# STM32H743IIT6.net
KiCad netlist of a schematic drawn in Altium Designer
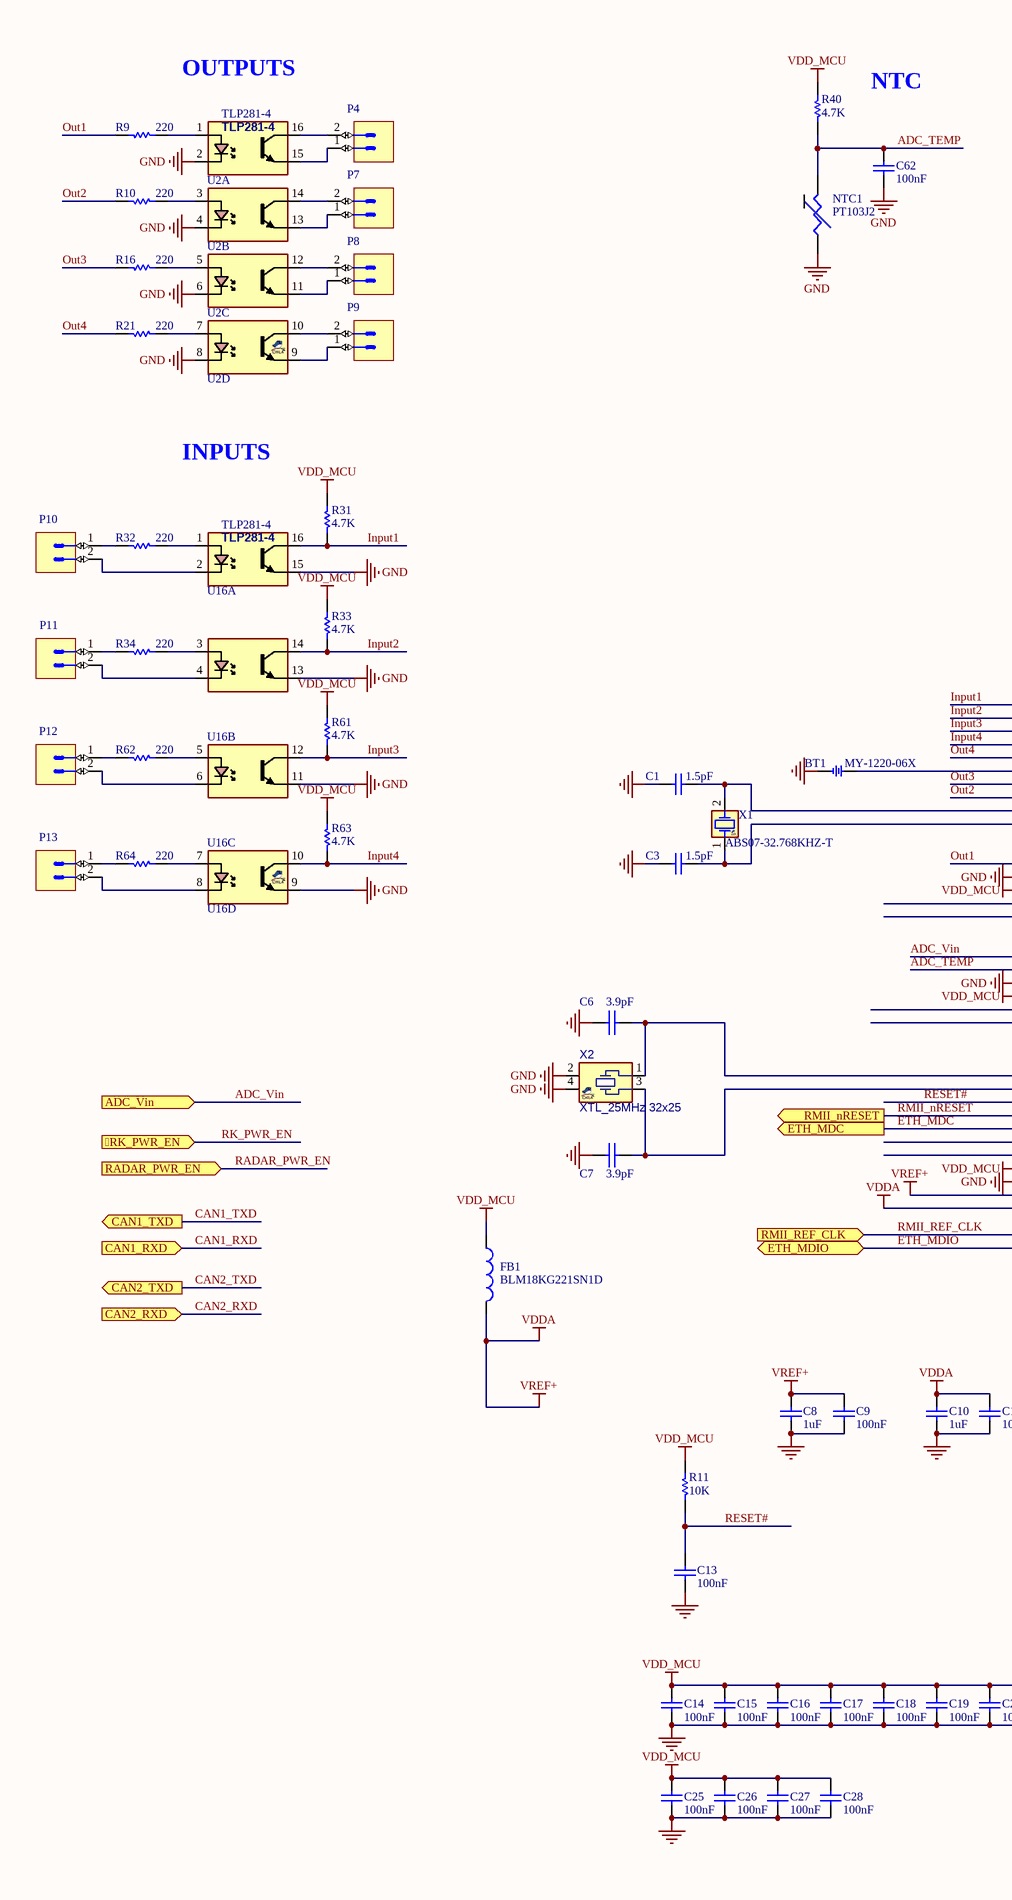
[diagram p0: STM32H743IIT6.SchDoc, left]
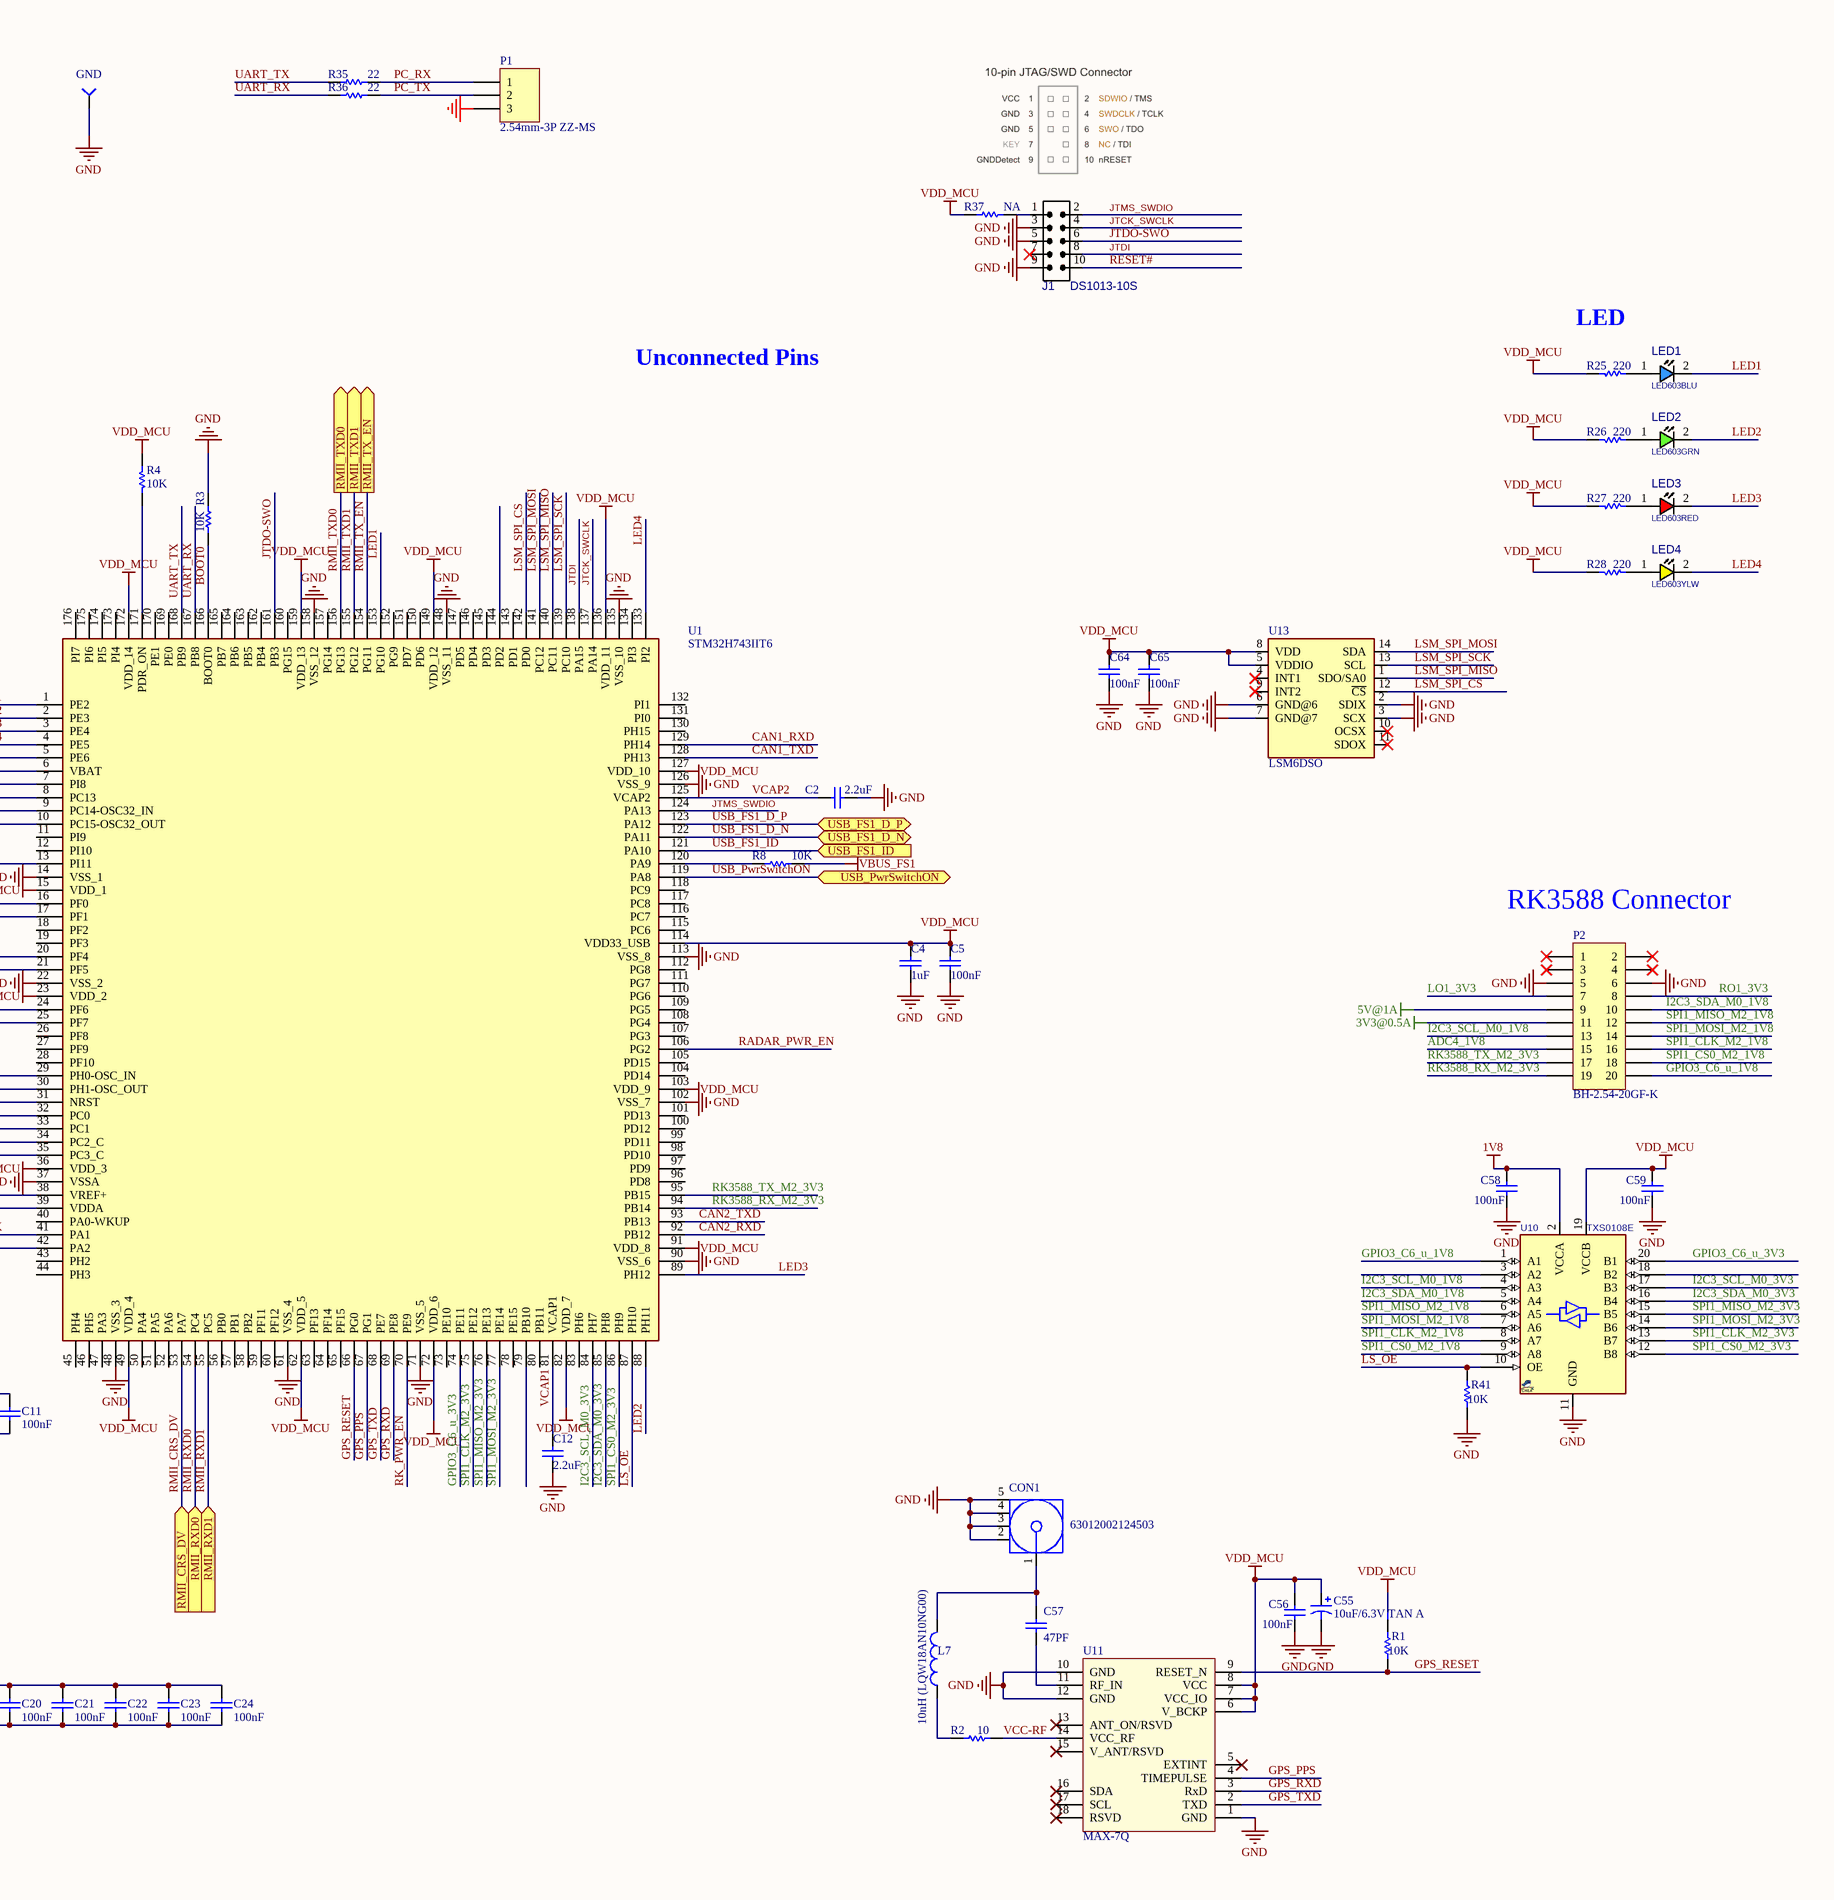
[diagram p1: STM32H743IIT6.SchDoc, right]

(export (version "E")
  (design (tool "Eeschema 10.0.6"))
  (components
    (comp (ref "BT1")
      (value "MY-1220-06X")
      (footprint "BAT-TH_MY-1220-01")
      (description "BATTERY HOLDER, CR1220")
      (libsource (lib "battery") (part "BATH_CR1220"))
    )
    (comp (ref "C1") (value "1.5pF") (footprint "C0603") (libsource (lib "MCD_TOOLS") (part "Capacitor_ST")))
    (comp (ref "C2")
      (value "2.2uF")
      (footprint "C0603")
      (fields (field (name "PUBLISHER") "Altium Limited"))
      (libsource (lib "Miscellaneous Devices") (part "Cap"))
    )
    (comp (ref "C3") (value "1.5pF") (footprint "C0603") (libsource (lib "MCD_TOOLS") (part "Capacitor_ST")))
    (comp (ref "C4")
      (value "1uF")
      (footprint "C0603")
      (fields (field (name "PUBLISHER") "Altium Limited"))
      (libsource (lib "Miscellaneous Devices") (part "Cap"))
    )
    (comp (ref "C5")
      (value "100nF")
      (footprint "C0603")
      (fields (field (name "PUBLISHER") "Altium Limited"))
      (libsource (lib "Miscellaneous Devices") (part "Cap"))
    )
    (comp (ref "C6") (value "3.9pF") (footprint "C0603") (libsource (lib "*") (part "CAP")))
    (comp (ref "C7") (value "3.9pF") (footprint "C0603") (libsource (lib "*") (part "CAP")))
    (comp (ref "C8")
      (value "1uF")
      (footprint "C0603")
      (fields (field (name "PUBLISHER") "Altium Limited"))
      (libsource (lib "Miscellaneous Devices") (part "Cap"))
    )
    (comp (ref "C9")
      (value "100nF")
      (footprint "C0603")
      (fields (field (name "PUBLISHER") "Altium Limited"))
      (libsource (lib "Miscellaneous Devices") (part "Cap"))
    )
    (comp (ref "C10")
      (value "1uF")
      (footprint "C0603")
      (fields (field (name "PUBLISHER") "Altium Limited"))
      (libsource (lib "Miscellaneous Devices") (part "Cap"))
    )
    (comp (ref "C11")
      (value "100nF")
      (footprint "C0603")
      (fields (field (name "PUBLISHER") "Altium Limited"))
      (libsource (lib "Miscellaneous Devices") (part "Cap"))
    )
    (comp (ref "C12")
      (value "2.2uF")
      (footprint "C0603")
      (fields (field (name "PUBLISHER") "Altium Limited"))
      (libsource (lib "Miscellaneous Devices") (part "Cap"))
    )
    (comp (ref "C13")
      (value "100nF")
      (footprint "C0603")
      (fields (field (name "PUBLISHER") "Altium Limited"))
      (libsource (lib "Miscellaneous Devices") (part "CAP"))
    )
    (comp (ref "C14")
      (value "100nF")
      (footprint "C0603")
      (fields (field (name "PUBLISHER") "Altium Limited"))
      (libsource (lib "Miscellaneous Devices") (part "CAP"))
    )
    (comp (ref "C15")
      (value "100nF")
      (footprint "C0603")
      (fields (field (name "PUBLISHER") "Altium Limited"))
      (libsource (lib "Miscellaneous Devices") (part "CAP"))
    )
    (comp (ref "C16")
      (value "100nF")
      (footprint "C0603")
      (fields (field (name "PUBLISHER") "Altium Limited"))
      (libsource (lib "Miscellaneous Devices") (part "CAP"))
    )
    (comp (ref "C17")
      (value "100nF")
      (footprint "C0603")
      (fields (field (name "PUBLISHER") "Altium Limited"))
      (libsource (lib "Miscellaneous Devices") (part "CAP"))
    )
    (comp (ref "C18")
      (value "100nF")
      (footprint "C0603")
      (fields (field (name "PUBLISHER") "Altium Limited"))
      (libsource (lib "Miscellaneous Devices") (part "CAP"))
    )
    (comp (ref "C19")
      (value "100nF")
      (footprint "C0603")
      (fields (field (name "PUBLISHER") "Altium Limited"))
      (libsource (lib "Miscellaneous Devices") (part "CAP"))
    )
    (comp (ref "C20")
      (value "100nF")
      (footprint "C0603")
      (fields (field (name "PUBLISHER") "Altium Limited"))
      (libsource (lib "Miscellaneous Devices") (part "CAP"))
    )
    (comp (ref "C21")
      (value "100nF")
      (footprint "C0603")
      (fields (field (name "PUBLISHER") "Altium Limited"))
      (libsource (lib "Miscellaneous Devices") (part "CAP"))
    )
    (comp (ref "C22")
      (value "100nF")
      (footprint "C0603")
      (fields (field (name "PUBLISHER") "Altium Limited"))
      (libsource (lib "Miscellaneous Devices") (part "CAP"))
    )
    (comp (ref "C23")
      (value "100nF")
      (footprint "C0603")
      (fields (field (name "PUBLISHER") "Altium Limited"))
      (libsource (lib "Miscellaneous Devices") (part "CAP"))
    )
    (comp (ref "C24")
      (value "100nF")
      (footprint "C0603")
      (fields (field (name "PUBLISHER") "Altium Limited"))
      (libsource (lib "Miscellaneous Devices") (part "CAP"))
    )
    (comp (ref "C25")
      (value "100nF")
      (footprint "C0603")
      (fields (field (name "PUBLISHER") "Altium Limited"))
      (libsource (lib "Miscellaneous Devices") (part "CAP"))
    )
    (comp (ref "C26")
      (value "100nF")
      (footprint "C0603")
      (fields (field (name "PUBLISHER") "Altium Limited"))
      (libsource (lib "Miscellaneous Devices") (part "CAP"))
    )
    (comp (ref "C27")
      (value "100nF")
      (footprint "C0603")
      (fields (field (name "PUBLISHER") "Altium Limited"))
      (libsource (lib "Miscellaneous Devices") (part "CAP"))
    )
    (comp (ref "C28")
      (value "100nF")
      (footprint "C0603")
      (fields (field (name "PUBLISHER") "Altium Limited"))
      (libsource (lib "Miscellaneous Devices") (part "CAP"))
    )
    (comp (ref "C55")
      (value "10uF/6.3V TAN A")
      (footprint "TANTALUM-A")
      (description "SMD Capacitor Tantalum 1UF 10V 10% 1206")
      (fields (field (name "MANUFACTURER") "Vishay or Panasonic") (field (name "PUBLISHER") "Altium Limited"))
      (libsource (lib "Miscellaneous Devices") (part "Cap Pol1"))
    )
    (comp (ref "C56")
      (value "100nF")
      (footprint "C0603")
      (description "Ceramic Capacitor")
      (fields (field (name "MANUFACTURER") "Vishay or Panasonic") (field (name "PUBLISHER") "Altium Limited"))
      (libsource (lib "Miscellaneous Devices") (part "Cap"))
    )
    (comp (ref "C57")
      (value "47PF")
      (footprint "C0603")
      (description "Chip Monolithic Ceramic Capacitor; SMD")
      (fields
        (field (name "MANUFACTURER") "Murata Electronics North America")
        (field (name "MANUFACTURER PART NUMBER") "GRM188R71C104KA01D")
      )
      (libsource (lib "Miscellaneous Devices") (part "Cap"))
    )
    (comp (ref "C58")
      (value "100nF")
      (footprint "C0603")
      (description "Ceramic Capacitor")
      (fields (field (name "MANUFACTURER") "Vishay or Panasonic") (field (name "PUBLISHER") "Altium Limited"))
      (libsource (lib "Miscellaneous Devices") (part "Cap"))
    )
    (comp (ref "C59")
      (value "100nF")
      (footprint "C0603")
      (description "Ceramic Capacitor")
      (fields (field (name "MANUFACTURER") "Vishay or Panasonic") (field (name "PUBLISHER") "Altium Limited"))
      (libsource (lib "Miscellaneous Devices") (part "Cap"))
    )
    (comp (ref "C62")
      (value "100nF")
      (footprint "C0603")
      (fields (field (name "PUBLISHER") "Altium Limited"))
      (libsource (lib "Miscellaneous Devices") (part "CAP"))
    )
    (comp (ref "C64")
      (value "100nF")
      (footprint "C0603")
      (fields (field (name "PUBLISHER") "Altium Limited"))
      (libsource (lib "Miscellaneous Devices") (part "Cap"))
    )
    (comp (ref "C65")
      (value "100nF")
      (footprint "C0603")
      (fields (field (name "PUBLISHER") "Altium Limited"))
      (libsource (lib "Miscellaneous Devices") (part "Cap"))
    )
    (comp (ref "CON1")
      (value "63012002124503")
      (footprint "SMA")
      (description "SMA Connector, PCB THT Jack, Straight")
      (fields
        (field (name "MANUFACTURER") "Amphenol Connex")
        (field (name "PARTNUMBER") "132134")
        (field (name "PUBLISHER") "Altium Limited")
      )
      (libsource (lib "Chin Nan RF Coaxial SMA") (part "19-46-2-TGG"))
    )
    (comp (ref "FB1")
      (value "BLM18KG221SN1D")
      (footprint "L0603E")
      (description "Ferrite Bead")
      (fields (field (name "PUBLISHER") "Altium Limited"))
      (libsource (lib "Miscellaneous Devices") (part "Inductor"))
    )
    (comp (ref "GND")
      (value "TEST POINT")
      (footprint "TEST_POINT")
      (libsource (lib "Tracker_MAIN_V1.01") (part "TEST POINT"))
    )
    (comp (ref "J1")
      (value "DS1013-10S")
      (footprint "IDC_2X5")
      (description "BOX HEADER 2*5 STRAIGHT")
      (libsource (lib "conn_header_idc") (part "IDC_2X5"))
    )
    (comp (ref "L7")
      (value "10nH (LQW18AN10NG00)")
      (footprint "L0603E")
      (description "FIXED IND 10NH 300MA 0.10 OHM")
      (fields
        (field (name "MANUFACTURER") "Murata Electronics North America")
        (field (name "MANUFACTURER PART NUMBER") "10nH/1%")
        (field (name "PART NUMBER") "10nH (LQW18AN10NG00)")
      )
      (libsource (lib "Main_Lib") (part "Inductor"))
    )
    (comp (ref "LED1")
      (value "LED603BLU")
      (footprint "LED0603BLU")
      (description "LED, SMD, 0603, BLUE")
      (fields (field (name "MANF") "MANF") (field (name "MANF_P#") "MANF_PART#"))
      (libsource (lib "led(diode)") (part "LED_SMD_0603_BLU"))
    )
    (comp (ref "LED2")
      (value "LED603GRN")
      (footprint "LED0603GRN")
      (description "LED, SMD, 0603, GREEN")
      (fields (field (name "MANF") "Kingbright") (field (name "MANF_P#") "APT1608SGC"))
      (libsource (lib "led(diode)") (part "LED_SMD_0603_GRN"))
    )
    (comp (ref "LED3")
      (value "LED603RED")
      (footprint "LED0603RED")
      (description "LED, SMD, 0603, RED")
      (fields (field (name "MANF") "MANF") (field (name "MANF_P#") "MANF_PART#"))
      (libsource (lib "led(diode)") (part "LED_SMD_0603_RED"))
    )
    (comp (ref "LED4")
      (value "LED603YLW")
      (footprint "LED0603YLW")
      (description "LED, SMD, 0603, YELLOW")
      (fields (field (name "MANF") "MANF") (field (name "MANF_P#") "MANF_PART#"))
      (libsource (lib "led(diode)") (part "LED_SMD_0603_YLW"))
    )
    (comp (ref "NTC1")
      (value "PT103J2")
      (footprint "HDR1X2")
      (description "THERMISTOR 10K OHM +/-0.20 C")
      (libsource (lib "J ABDAR-Altium-LibV1") (part "NTC power"))
    )
    (comp (ref "P1")
      (value "2.54mm-3P ZZ-MS")
      (footprint "xh-3")
      (description "1x3P XH 2.54mm Male Straight Wire To Board Connector")
      (fields (field (name "PUBLISHER") "Altium Limited"))
      (libsource (lib "Miscellaneous Connectors") (part "Header 3"))
    )
    (comp (ref "P2")
      (value "BH-2.54-20GF-K")
      (footprint "HDR2X10")
      (description "BOX HEADER 2*10 STRAIGHT")
      (fields (field (name "PUBLISHER") "Altium Limited"))
      (libsource (lib "Miscellaneous Connectors") (part "Header 10X2"))
    )
    (comp (ref "P4")
      (value "JST PH 2mm 2P RIGHT")
      (footprint "JST B2B-PH-K")
      (description "JST PH 2P RIGHT")
      (fields
        (field (name "PART NUMBER") "PHOENIX_1803426")
        (field (name "MANUFACTURER") "PHOENIX CONTACT")
        (field (name "AUTHOR") "CERN DEM JLC")
      )
      (libsource (lib "") (part "Connector 2 Male_1"))
    )
    (comp (ref "P7")
      (value "JST PH 2mm 2P RIGHT")
      (footprint "JST B2B-PH-K")
      (description "JST PH 2P RIGHT")
      (fields
        (field (name "PART NUMBER") "PHOENIX_1803426")
        (field (name "MANUFACTURER") "PHOENIX CONTACT")
        (field (name "AUTHOR") "CERN DEM JLC")
      )
      (libsource (lib "") (part "Connector 2 Male_1"))
    )
    (comp (ref "P8")
      (value "JST PH 2mm 2P RIGHT")
      (footprint "JST B2B-PH-K")
      (description "JST PH 2P RIGHT")
      (fields
        (field (name "PART NUMBER") "PHOENIX_1803426")
        (field (name "MANUFACTURER") "PHOENIX CONTACT")
        (field (name "AUTHOR") "CERN DEM JLC")
      )
      (libsource (lib "") (part "Connector 2 Male_1"))
    )
    (comp (ref "P9")
      (value "JST PH 2mm 2P RIGHT")
      (footprint "JST B2B-PH-K")
      (description "JST PH 2P RIGHT")
      (fields
        (field (name "PART NUMBER") "PHOENIX_1803426")
        (field (name "MANUFACTURER") "PHOENIX CONTACT")
        (field (name "AUTHOR") "CERN DEM JLC")
      )
      (libsource (lib "") (part "Connector 2 Male_1"))
    )
    (comp (ref "P10")
      (value "JST PH 2mm 2P RIGHT")
      (footprint "JST B2B-PH-K")
      (description "JST PH 2P RIGHT")
      (fields
        (field (name "PART NUMBER") "PHOENIX_1803426")
        (field (name "MANUFACTURER") "PHOENIX CONTACT")
        (field (name "AUTHOR") "CERN DEM JLC")
      )
      (libsource (lib "Connectors") (part "Connector 2 Male"))
    )
    (comp (ref "P11")
      (value "JST PH 2mm 2P RIGHT")
      (footprint "JST B2B-PH-K")
      (description "JST PH 2P RIGHT")
      (fields
        (field (name "PART NUMBER") "PHOENIX_1803426")
        (field (name "MANUFACTURER") "PHOENIX CONTACT")
        (field (name "AUTHOR") "CERN DEM JLC")
      )
      (libsource (lib "Connectors") (part "Connector 2 Male"))
    )
    (comp (ref "P12")
      (value "JST PH 2mm 2P RIGHT")
      (footprint "JST B2B-PH-K")
      (description "JST PH 2P RIGHT")
      (fields
        (field (name "PART NUMBER") "PHOENIX_1803426")
        (field (name "MANUFACTURER") "PHOENIX CONTACT")
        (field (name "AUTHOR") "CERN DEM JLC")
      )
      (libsource (lib "Connectors") (part "Connector 2 Male"))
    )
    (comp (ref "P13")
      (value "JST PH 2mm 2P RIGHT")
      (footprint "JST B2B-PH-K")
      (description "JST PH 2P RIGHT")
      (fields
        (field (name "PART NUMBER") "PHOENIX_1803426")
        (field (name "MANUFACTURER") "PHOENIX CONTACT")
        (field (name "AUTHOR") "CERN DEM JLC")
      )
      (libsource (lib "Connectors") (part "Connector 2 Male"))
    )
    (comp (ref "R1")
      (value "10K")
      (footprint "R0603")
      (description "Resistor: thick film; SMD")
      (fields (field (name "MANUFACTURER") "Yageo"))
      (libsource (lib "") (part "Res1_1"))
    )
    (comp (ref "R2")
      (value "10")
      (footprint "R0603")
      (description "Resistor: thick film; SMD")
      (fields (field (name "MANUFACTURER") "Yageo") (field (name "PART NUMBER") "10R"))
      (libsource (lib "") (part "Res1_1"))
    )
    (comp (ref "R3")
      (value "10K")
      (footprint "R0603")
      (fields (field (name "PUBLISHER") "Altium Limited"))
      (libsource (lib "Miscellaneous Devices") (part "res1"))
    )
    (comp (ref "R4")
      (value "10K")
      (footprint "R0603")
      (fields (field (name "PUBLISHER") "Altium Limited"))
      (libsource (lib "Miscellaneous Devices") (part "Res1"))
    )
    (comp (ref "R8")
      (value "10K")
      (footprint "R0603")
      (fields (field (name "PUBLISHER") "Altium Limited"))
      (libsource (lib "Miscellaneous Devices") (part "Res1"))
    )
    (comp (ref "R9")
      (value "220")
      (footprint "R0603")
      (fields (field (name "PUBLISHER") "Altium Limited"))
      (libsource (lib "Miscellaneous Devices") (part "Res1"))
    )
    (comp (ref "R10")
      (value "220")
      (footprint "R0603")
      (fields (field (name "PUBLISHER") "Altium Limited"))
      (libsource (lib "Miscellaneous Devices") (part "Res1"))
    )
    (comp (ref "R11")
      (value "10K")
      (footprint "R0603")
      (fields (field (name "PUBLISHER") "Altium Limited"))
      (libsource (lib "Miscellaneous Devices") (part "Res1"))
    )
    (comp (ref "R16")
      (value "220")
      (footprint "R0603")
      (fields (field (name "PUBLISHER") "Altium Limited"))
      (libsource (lib "Miscellaneous Devices") (part "Res1"))
    )
    (comp (ref "R21")
      (value "220")
      (footprint "R0603")
      (fields (field (name "PUBLISHER") "Altium Limited"))
      (libsource (lib "Miscellaneous Devices") (part "Res1"))
    )
    (comp (ref "R25")
      (value "220")
      (footprint "R0603")
      (fields (field (name "PUBLISHER") "Altium Limited"))
      (libsource (lib "Miscellaneous Devices") (part "Res1"))
    )
    (comp (ref "R26")
      (value "220")
      (footprint "R0603")
      (fields (field (name "PUBLISHER") "Altium Limited"))
      (libsource (lib "Miscellaneous Devices") (part "Res1"))
    )
    (comp (ref "R27")
      (value "220")
      (footprint "R0603")
      (fields (field (name "PUBLISHER") "Altium Limited"))
      (libsource (lib "Miscellaneous Devices") (part "Res1"))
    )
    (comp (ref "R28")
      (value "220")
      (footprint "R0603")
      (fields (field (name "PUBLISHER") "Altium Limited"))
      (libsource (lib "Miscellaneous Devices") (part "Res1"))
    )
    (comp (ref "R31")
      (value "4.7K")
      (footprint "R0603")
      (fields (field (name "PUBLISHER") "Altium Limited"))
      (libsource (lib "Miscellaneous Devices") (part "Res1"))
    )
    (comp (ref "R32")
      (value "220")
      (footprint "R0603")
      (fields (field (name "PUBLISHER") "Altium Limited"))
      (libsource (lib "Miscellaneous Devices") (part "Res1"))
    )
    (comp (ref "R33")
      (value "4.7K")
      (footprint "R0603")
      (fields (field (name "PUBLISHER") "Altium Limited"))
      (libsource (lib "Miscellaneous Devices") (part "Res1"))
    )
    (comp (ref "R34")
      (value "220")
      (footprint "R0603")
      (fields (field (name "PUBLISHER") "Altium Limited"))
      (libsource (lib "Miscellaneous Devices") (part "Res1"))
    )
    (comp (ref "R35")
      (value "22")
      (footprint "R0603")
      (fields (field (name "PUBLISHER") "Altium Limited"))
      (libsource (lib "Miscellaneous Devices") (part "res1"))
    )
    (comp (ref "R36")
      (value "22")
      (footprint "R0603")
      (fields (field (name "PUBLISHER") "Altium Limited"))
      (libsource (lib "Miscellaneous Devices") (part "res1"))
    )
    (comp (ref "R37")
      (value "NA")
      (footprint "R0603")
      (fields (field (name "PUBLISHER") "Altium Limited"))
      (libsource (lib "Miscellaneous Devices") (part "Res1"))
    )
    (comp (ref "R40")
      (value "4.7K")
      (footprint "R0603")
      (fields (field (name "PUBLISHER") "Altium Limited"))
      (libsource (lib "Miscellaneous Devices") (part "Res1"))
    )
    (comp (ref "R41")
      (value "10K")
      (footprint "R0603")
      (description "Resistor: thick film; SMD")
      (fields (field (name "MANUFACTURER") "Yageo"))
      (libsource (lib "") (part "Res1_1"))
    )
    (comp (ref "R61")
      (value "4.7K")
      (footprint "R0603")
      (fields (field (name "PUBLISHER") "Altium Limited"))
      (libsource (lib "Miscellaneous Devices") (part "Res1"))
    )
    (comp (ref "R62")
      (value "220")
      (footprint "R0603")
      (fields (field (name "PUBLISHER") "Altium Limited"))
      (libsource (lib "Miscellaneous Devices") (part "Res1"))
    )
    (comp (ref "R63")
      (value "4.7K")
      (footprint "R0603")
      (fields (field (name "PUBLISHER") "Altium Limited"))
      (libsource (lib "Miscellaneous Devices") (part "Res1"))
    )
    (comp (ref "R64")
      (value "220")
      (footprint "R0603")
      (fields (field (name "PUBLISHER") "Altium Limited"))
      (libsource (lib "Miscellaneous Devices") (part "Res1"))
    )
    (comp (ref "U1")
      (value "STM32H743IIT6")
      (footprint "QFP50P2600X2600X160-176N")
      (description "Integrated Circuit")
      (fields (field (name "MOUSER PART NUMBER") "511-STM32H743IIT6"))
      (libsource (lib "*") (part "STM32H743IIT6"))
    )
    (comp (ref "U2")
      (value "TLP281-4")
      (footprint "SO_16")
      (description "OPTOCOUPLER, TRANSISTOR, QUAD")
      (fields (field (name "MANF_P#") "TLP281-4A"))
      (libsource (lib "optocoupler") (part "OPTC_TR16P_TLP281-4_SMD"))
    )
    (comp (ref "U10")
      (value "TXS0108E")
      (footprint "SOG65_20")
      (description "Level Translator, Octal")
      (fields (field (name "MANF") "Texas Instruments") (field (name "MANF_P#") "TXS0108EPWR"))
      (libsource (lib "buffer_digital") (part "TXS0108_SSOP20"))
    )
    (comp (ref "U11")
      (value "MAX-7Q")
      (footprint "MAX")
      (description "GPS chip module MAX-7Q")
      (fields (field (name "PART NUMBER") "EPP0910") (field (name "MANUFACTURER") "NULL"))
      (libsource (lib "Main_Lib") (part "MAX"))
    )
    (comp (ref "U13")
      (value "LSM6DSO")
      (footprint "LGA-14_L3.0-W2.5-P0.50-TL")
      (description "SPARKFUN 6 DEGREES OF FREEDOM BR")
      (fields (field (name "MF") "STMicroelectronics"))
      (libsource (lib "LSM6DSO") (part "LSM6DSO"))
    )
    (comp (ref "U16")
      (value "TLP281-4")
      (footprint "SO_16")
      (description "OPTOCOUPLER, TRANSISTOR, QUAD")
      (fields (field (name "MANF_P#") "TLP281-4A"))
      (libsource (lib "optocoupler") (part "OPTC_TR16P_TLP281-4_SMD"))
    )
    (comp (ref "X1")
      (value "ABS07-32.768KHZ-T")
      (footprint "XTL_2_3215")
      (description "Crystal, 32.768KHz, 3pF, 20PPM")
      (fields (field (name "MANF") "ABRACON") (field (name "MANF_P#") "ABS07W-32.768kHz-D-2-T"))
      (libsource (lib "crystal") (part "XTL_2_32.768_3215A"))
    )
    (comp (ref "X2")
      (value "XTL_25MHz 32x25")
      (footprint "XTL_4_3225")
      (description "CRYSTAL 25.00 MHZ 18pF, 10PPM")
      (fields (field (name "MANF") "EPSON") (field (name "MANF_P#") "TSX-3225 25.0000MF10P-C3"))
      (libsource (lib "crystal") (part "XTL_4_25MHz_3225"))
    )
  )
  (nets
    (net (code "1") (name "/ADC4_1V8") (class "Default")
      (node (ref "P2") (pin "15") (pinfunction "15_15") (pintype "passive"))
    )
    (net (code "2") (name "/ADC_TEMP") (class "Default")
      (node (ref "C62") (pin "2") (pinfunction "2_2") (pintype "passive"))
      (node (ref "NTC1") (pin "2") (pintype "passive"))
      (node (ref "R40") (pin "2") (pinfunction "2_2") (pintype "passive"))
      (node (ref "U1") (pin "21") (pinfunction "PF5_21") (pintype "passive"))
    )
    (net (code "3") (name "/ADC_Vin") (class "Default")
      (node (ref "U1") (pin "20") (pinfunction "PF4_20") (pintype "passive"))
    )
    (net (code "4") (name "/BOOT0") (class "Default")
      (node (ref "R3") (pin "1") (pinfunction "1_1") (pintype "passive"))
      (node (ref "U1") (pin "166") (pinfunction "BOOT0_166") (pintype "passive"))
    )
    (net (code "5") (name "/CAN1_RXD") (class "Default")
      (node (ref "U1") (pin "129") (pinfunction "PH14_129") (pintype "passive"))
    )
    (net (code "6") (name "/CAN1_TXD") (class "Default")
      (node (ref "U1") (pin "128") (pinfunction "PH13_128") (pintype "passive"))
    )
    (net (code "7") (name "/CAN2_RXD") (class "Default")
      (node (ref "U1") (pin "92") (pinfunction "PB12_92") (pintype "passive"))
    )
    (net (code "8") (name "/CAN2_TXD") (class "Default")
      (node (ref "U1") (pin "93") (pinfunction "PB13_93") (pintype "passive"))
    )
    (net (code "9") (name "/ETH_MDC") (class "Default")
      (node (ref "U1") (pin "33") (pinfunction "PC1_33") (pintype "passive"))
    )
    (net (code "10") (name "/ETH_MDIO") (class "Default")
      (node (ref "U1") (pin "42") (pinfunction "PA2_42") (pintype "passive"))
    )
    (net (code "11") (name "/GPIO3_C6_u_1V8") (class "Default")
      (node (ref "P2") (pin "20") (pinfunction "20_20") (pintype "passive"))
      (node (ref "U10") (pin "1") (pinfunction "A1_1") (pintype "bidirectional"))
    )
    (net (code "12") (name "/GPIO3_C6_u_3V3") (class "Default")
      (node (ref "U1") (pin "74") (pinfunction "PE11_74") (pintype "passive"))
      (node (ref "U10") (pin "20") (pinfunction "B1_20") (pintype "bidirectional"))
    )
    (net (code "13") (name "/GPS_PPS") (class "Default")
      (node (ref "U1") (pin "67") (pinfunction "PG1_67") (pintype "passive"))
      (node (ref "U11") (pin "4") (pinfunction "TIMEPULSE_4") (pintype "passive"))
    )
    (net (code "14") (name "/GPS_RESET") (class "Default")
      (node (ref "R1") (pin "1") (pinfunction "1_1") (pintype "passive"))
      (node (ref "U1") (pin "66") (pinfunction "PG0_66") (pintype "passive"))
      (node (ref "U11") (pin "9") (pinfunction "RESET_N_9") (pintype "passive"))
    )
    (net (code "15") (name "/GPS_RXD") (class "Default")
      (node (ref "U1") (pin "69") (pinfunction "PE8_69") (pintype "passive"))
      (node (ref "U11") (pin "3") (pinfunction "RxD_3") (pintype "passive"))
    )
    (net (code "16") (name "/GPS_TXD") (class "Default")
      (node (ref "U1") (pin "68") (pinfunction "PE7_68") (pintype "passive"))
      (node (ref "U11") (pin "2") (pinfunction "TXD_2") (pintype "passive"))
    )
    (net (code "17") (name "/I2C3_SCL_M0_1V8") (class "Default")
      (node (ref "P2") (pin "13") (pinfunction "13_13") (pintype "passive"))
      (node (ref "U10") (pin "4") (pinfunction "A3_4") (pintype "bidirectional"))
    )
    (net (code "18") (name "/I2C3_SCL_M0_3V3") (class "Default")
      (node (ref "U1") (pin "84") (pinfunction "PH7_84") (pintype "passive"))
      (node (ref "U10") (pin "17") (pinfunction "B3_17") (pintype "bidirectional"))
    )
    (net (code "19") (name "/I2C3_SDA_M0_1V8") (class "Default")
      (node (ref "P2") (pin "10") (pinfunction "10_10") (pintype "passive"))
      (node (ref "U10") (pin "5") (pinfunction "A4_5") (pintype "bidirectional"))
    )
    (net (code "20") (name "/I2C3_SDA_M0_3V3") (class "Default")
      (node (ref "U1") (pin "85") (pinfunction "PH8_85") (pintype "passive"))
      (node (ref "U10") (pin "16") (pinfunction "B4_16") (pintype "bidirectional"))
    )
    (net (code "21") (name "/Input1") (class "Default")
      (node (ref "R31") (pin "1") (pinfunction "1_1") (pintype "passive"))
      (node (ref "U1") (pin "1") (pinfunction "PE2_1") (pintype "passive"))
      (node (ref "U16") (pin "16") (pinfunction "16_16") (pintype "power_in"))
    )
    (net (code "22") (name "/Input2") (class "Default")
      (node (ref "R33") (pin "1") (pinfunction "1_1") (pintype "passive"))
      (node (ref "U1") (pin "2") (pinfunction "PE3_2") (pintype "passive"))
      (node (ref "U16") (pin "14") (pinfunction "14_14") (pintype "power_in"))
    )
    (net (code "23") (name "/Input3") (class "Default")
      (node (ref "R61") (pin "1") (pinfunction "1_1") (pintype "passive"))
      (node (ref "U1") (pin "3") (pinfunction "PE4_3") (pintype "passive"))
      (node (ref "U16") (pin "12") (pinfunction "12_12") (pintype "power_in"))
    )
    (net (code "24") (name "/Input4") (class "Default")
      (node (ref "R63") (pin "1") (pinfunction "1_1") (pintype "passive"))
      (node (ref "U1") (pin "4") (pinfunction "PE5_4") (pintype "passive"))
      (node (ref "U16") (pin "10") (pinfunction "10_10") (pintype "power_in"))
    )
    (net (code "25") (name "/JTCK_SWCLK") (class "Default")
      (node (ref "J1") (pin "4") (pinfunction "4_4") (pintype "passive"))
      (node (ref "U1") (pin "137") (pinfunction "PA14_137") (pintype "passive"))
    )
    (net (code "26") (name "/JTDI") (class "Default")
      (node (ref "J1") (pin "8") (pinfunction "8_8") (pintype "passive"))
      (node (ref "U1") (pin "138") (pinfunction "PA15_138") (pintype "passive"))
    )
    (net (code "27") (name "/JTDO-SWO") (class "Default")
      (node (ref "J1") (pin "6") (pinfunction "6_6") (pintype "passive"))
      (node (ref "U1") (pin "161") (pinfunction "PB3_161") (pintype "passive"))
    )
    (net (code "28") (name "/JTMS_SWDIO") (class "Default")
      (node (ref "J1") (pin "2") (pinfunction "2_2") (pintype "passive"))
      (node (ref "U1") (pin "124") (pinfunction "PA13_124") (pintype "passive"))
    )
    (net (code "29") (name "/LED1") (class "Default")
      (node (ref "LED1") (pin "2") (pinfunction "CATHODE_2") (pintype "passive"))
      (node (ref "U1") (pin "153") (pinfunction "PG10_153") (pintype "passive"))
    )
    (net (code "30") (name "/LED2") (class "Default")
      (node (ref "LED2") (pin "2") (pinfunction "CATHODE_2") (pintype "passive"))
      (node (ref "U1") (pin "88") (pinfunction "PH11_88") (pintype "passive"))
    )
    (net (code "31") (name "/LED3") (class "Default")
      (node (ref "LED3") (pin "2") (pinfunction "CATHODE_2") (pintype "passive"))
      (node (ref "U1") (pin "89") (pinfunction "PH12_89") (pintype "passive"))
    )
    (net (code "32") (name "/LED4") (class "Default")
      (node (ref "LED4") (pin "2") (pinfunction "CATHODE_2") (pintype "passive"))
      (node (ref "U1") (pin "133") (pinfunction "PI2_133") (pintype "passive"))
    )
    (net (code "33") (name "/LO1_3V3") (class "Default")
      (node (ref "P2") (pin "7") (pinfunction "7_7") (pintype "passive"))
    )
    (net (code "34") (name "/LSM_SPI_CS") (class "Default")
      (node (ref "U1") (pin "142") (pinfunction "PD0_142") (pintype "passive"))
      (node (ref "U13") (pin "12") (pinfunction "~{CS}_12") (pintype "bidirectional"))
    )
    (net (code "35") (name "/LSM_SPI_MISO") (class "Default")
      (node (ref "U1") (pin "140") (pinfunction "PC11_140") (pintype "passive"))
      (node (ref "U13") (pin "1") (pinfunction "SDO/SA0_1") (pintype "bidirectional"))
    )
    (net (code "36") (name "/LSM_SPI_MOSI") (class "Default")
      (node (ref "U1") (pin "141") (pinfunction "PC12_141") (pintype "passive"))
      (node (ref "U13") (pin "14") (pinfunction "SDA_14") (pintype "bidirectional"))
    )
    (net (code "37") (name "/LSM_SPI_SCK") (class "Default")
      (node (ref "U1") (pin "139") (pinfunction "PC10_139") (pintype "passive"))
      (node (ref "U13") (pin "13") (pinfunction "SCL_13") (pintype "bidirectional"))
    )
    (net (code "38") (name "/LS_OE") (class "Default")
      (node (ref "R41") (pin "2") (pinfunction "2_2") (pintype "passive"))
      (node (ref "U1") (pin "87") (pinfunction "PH10_87") (pintype "passive"))
      (node (ref "U10") (pin "10") (pinfunction "OE_10") (pintype "input"))
    )
    (net (code "39") (name "/Out1") (class "Default")
      (node (ref "R9") (pin "1") (pinfunction "1_1") (pintype "passive"))
      (node (ref "U1") (pin "13") (pinfunction "PI11_13") (pintype "passive"))
    )
    (net (code "40") (name "/Out2") (class "Default")
      (node (ref "R10") (pin "1") (pinfunction "1_1") (pintype "passive"))
      (node (ref "U1") (pin "8") (pinfunction "PC13_8") (pintype "passive"))
    )
    (net (code "41") (name "/Out3") (class "Default")
      (node (ref "R16") (pin "1") (pinfunction "1_1") (pintype "passive"))
      (node (ref "U1") (pin "7") (pinfunction "PI8_7") (pintype "passive"))
    )
    (net (code "42") (name "/Out4") (class "Default")
      (node (ref "R21") (pin "1") (pinfunction "1_1") (pintype "passive"))
      (node (ref "U1") (pin "5") (pinfunction "PE6_5") (pintype "passive"))
    )
    (net (code "43") (name "/PC_RX") (class "Default")
      (node (ref "P1") (pin "1") (pinfunction "1_1") (pintype "passive"))
      (node (ref "R35") (pin "1") (pinfunction "1_1") (pintype "passive"))
    )
    (net (code "44") (name "/PC_TX") (class "Default")
      (node (ref "P1") (pin "2") (pinfunction "2_2") (pintype "passive"))
      (node (ref "R36") (pin "1") (pinfunction "1_1") (pintype "passive"))
    )
    (net (code "45") (name "/RADAR_PWR_EN") (class "Default")
      (node (ref "U1") (pin "106") (pinfunction "PG2_106") (pintype "passive"))
    )
    (net (code "46") (name "/RESET#") (class "Default")
      (node (ref "C13") (pin "2") (pinfunction "2_2") (pintype "passive"))
      (node (ref "J1") (pin "10") (pinfunction "10_10") (pintype "passive"))
      (node (ref "R11") (pin "2") (pinfunction "2_2") (pintype "passive"))
      (node (ref "U1") (pin "31") (pinfunction "NRST_31") (pintype "passive"))
    )
    (net (code "47") (name "/RK3588_RX_M2_3V3") (class "Default")
      (node (ref "P2") (pin "19") (pinfunction "19_19") (pintype "passive"))
      (node (ref "U1") (pin "94") (pinfunction "PB14_94") (pintype "passive"))
    )
    (net (code "48") (name "/RK3588_TX_M2_3V3") (class "Default")
      (node (ref "P2") (pin "17") (pinfunction "17_17") (pintype "passive"))
      (node (ref "U1") (pin "95") (pinfunction "PB15_95") (pintype "passive"))
    )
    (net (code "49") (name "/RK_PWR_EN") (class "Default")
      (node (ref "U1") (pin "70") (pinfunction "PE9_70") (pintype "passive"))
    )
    (net (code "50") (name "/RMII_CRS_DV") (class "Default")
      (node (ref "U1") (pin "53") (pinfunction "PA7_53") (pintype "passive"))
    )
    (net (code "51") (name "/RMII_REF_CLK") (class "Default")
      (node (ref "U1") (pin "41") (pinfunction "PA1_41") (pintype "passive"))
    )
    (net (code "52") (name "/RMII_RXD0") (class "Default")
      (node (ref "U1") (pin "54") (pinfunction "PC4_54") (pintype "passive"))
    )
    (net (code "53") (name "/RMII_RXD1") (class "Default")
      (node (ref "U1") (pin "55") (pinfunction "PC5_55") (pintype "passive"))
    )
    (net (code "54") (name "/RMII_TXD0") (class "Default")
      (node (ref "U1") (pin "156") (pinfunction "PG13_156") (pintype "passive"))
    )
    (net (code "55") (name "/RMII_TXD1") (class "Default")
      (node (ref "U1") (pin "155") (pinfunction "PG12_155") (pintype "passive"))
    )
    (net (code "56") (name "/RMII_TX_EN") (class "Default")
      (node (ref "U1") (pin "154") (pinfunction "PG11_154") (pintype "passive"))
    )
    (net (code "57") (name "/RMII_nRESET") (class "Default")
      (node (ref "U1") (pin "32") (pinfunction "PC0_32") (pintype "passive"))
    )
    (net (code "58") (name "/RO1_3V3") (class "Default")
      (node (ref "P2") (pin "8") (pinfunction "8_8") (pintype "passive"))
    )
    (net (code "59") (name "/SPI1_CLK_M2_1V8") (class "Default")
      (node (ref "P2") (pin "16") (pinfunction "16_16") (pintype "passive"))
      (node (ref "U10") (pin "8") (pinfunction "A7_8") (pintype "bidirectional"))
    )
    (net (code "60") (name "/SPI1_CLK_M2_3V3") (class "Default")
      (node (ref "U1") (pin "75") (pinfunction "PE12_75") (pintype "passive"))
      (node (ref "U10") (pin "13") (pinfunction "B7_13") (pintype "bidirectional"))
    )
    (net (code "61") (name "/SPI1_CS0_M2_1V8") (class "Default")
      (node (ref "P2") (pin "18") (pinfunction "18_18") (pintype "passive"))
      (node (ref "U10") (pin "9") (pinfunction "A8_9") (pintype "bidirectional"))
    )
    (net (code "62") (name "/SPI1_CS0_M2_3V3") (class "Default")
      (node (ref "U1") (pin "86") (pinfunction "PH9_86") (pintype "passive"))
      (node (ref "U10") (pin "12") (pinfunction "B8_12") (pintype "bidirectional"))
    )
    (net (code "63") (name "/SPI1_MISO_M2_1V8") (class "Default")
      (node (ref "P2") (pin "12") (pinfunction "12_12") (pintype "passive"))
      (node (ref "U10") (pin "6") (pinfunction "A5_6") (pintype "bidirectional"))
    )
    (net (code "64") (name "/SPI1_MISO_M2_3V3") (class "Default")
      (node (ref "U1") (pin "76") (pinfunction "PE13_76") (pintype "passive"))
      (node (ref "U10") (pin "15") (pinfunction "B5_15") (pintype "bidirectional"))
    )
    (net (code "65") (name "/SPI1_MOSI_M2_1V8") (class "Default")
      (node (ref "P2") (pin "14") (pinfunction "14_14") (pintype "passive"))
      (node (ref "U10") (pin "7") (pinfunction "A6_7") (pintype "bidirectional"))
    )
    (net (code "66") (name "/SPI1_MOSI_M2_3V3") (class "Default")
      (node (ref "U1") (pin "77") (pinfunction "PE14_77") (pintype "passive"))
      (node (ref "U10") (pin "14") (pinfunction "B6_14") (pintype "bidirectional"))
    )
    (net (code "67") (name "/UART_RX") (class "Default")
      (node (ref "R36") (pin "2") (pinfunction "2_2") (pintype "passive"))
      (node (ref "U1") (pin "167") (pinfunction "PB8_167") (pintype "passive"))
    )
    (net (code "68") (name "/UART_TX") (class "Default")
      (node (ref "R35") (pin "2") (pinfunction "2_2") (pintype "passive"))
      (node (ref "U1") (pin "168") (pinfunction "PB9_168") (pintype "passive"))
    )
    (net (code "69") (name "/USB_FS1_D_N") (class "Default")
      (node (ref "U1") (pin "122") (pinfunction "PA11_122") (pintype "passive"))
    )
    (net (code "70") (name "/USB_FS1_D_P") (class "Default")
      (node (ref "U1") (pin "123") (pinfunction "PA12_123") (pintype "passive"))
    )
    (net (code "71") (name "/USB_FS1_ID") (class "Default")
      (node (ref "U1") (pin "121") (pinfunction "PA10_121") (pintype "passive"))
    )
    (net (code "72") (name "/USB_PwrSwitchON") (class "Default")
      (node (ref "U1") (pin "119") (pinfunction "PA8_119") (pintype "passive"))
    )
    (net (code "73") (name "/VCAP1") (class "Default")
      (node (ref "C12") (pin "2") (pinfunction "2_2") (pintype "passive"))
      (node (ref "U1") (pin "81") (pinfunction "VCAP1_81") (pintype "power_in"))
    )
    (net (code "74") (name "/VCAP2") (class "Default")
      (node (ref "C2") (pin "1") (pinfunction "1_1") (pintype "passive"))
      (node (ref "U1") (pin "125") (pinfunction "VCAP2_125") (pintype "power_in"))
    )
    (net (code "75") (name "/VCC-RF") (class "Default")
      (node (ref "R2") (pin "1") (pinfunction "1_1") (pintype "passive"))
      (node (ref "U11") (pin "14") (pinfunction "VCC_RF_14") (pintype "passive"))
    )
    (net (code "76") (name "1V8") (class "Default")
      (node (ref "C58") (pin "1") (pinfunction "1_1") (pintype "passive"))
      (node (ref "U10") (pin "2") (pinfunction "VCCA_2") (pintype "power_in"))
    )
    (net (code "77") (name "3V3@0.5A") (class "Default")
      (node (ref "P2") (pin "11") (pinfunction "11_11") (pintype "passive"))
    )
    (net (code "78") (name "5V@1A") (class "Default")
      (node (ref "P2") (pin "9") (pinfunction "9_9") (pintype "passive"))
    )
    (net (code "79") (name "GND") (class "Default")
      (node (ref "BT1") (pin "2") (pinfunction "2_2") (pintype "passive"))
      (node (ref "C1") (pin "2") (pinfunction "2_2") (pintype "passive"))
      (node (ref "C10") (pin "1") (pinfunction "1_1") (pintype "passive"))
      (node (ref "C11") (pin "1") (pinfunction "1_1") (pintype "passive"))
      (node (ref "C12") (pin "1") (pinfunction "1_1") (pintype "passive"))
      (node (ref "C13") (pin "1") (pinfunction "1_1") (pintype "passive"))
      (node (ref "C14") (pin "2") (pinfunction "2_2") (pintype "passive"))
      (node (ref "C15") (pin "2") (pinfunction "2_2") (pintype "passive"))
      (node (ref "C16") (pin "2") (pinfunction "2_2") (pintype "passive"))
      (node (ref "C17") (pin "2") (pinfunction "2_2") (pintype "passive"))
      (node (ref "C18") (pin "2") (pinfunction "2_2") (pintype "passive"))
      (node (ref "C19") (pin "2") (pinfunction "2_2") (pintype "passive"))
      (node (ref "C2") (pin "2") (pinfunction "2_2") (pintype "passive"))
      (node (ref "C20") (pin "2") (pinfunction "2_2") (pintype "passive"))
      (node (ref "C21") (pin "2") (pinfunction "2_2") (pintype "passive"))
      (node (ref "C22") (pin "2") (pinfunction "2_2") (pintype "passive"))
      (node (ref "C23") (pin "2") (pinfunction "2_2") (pintype "passive"))
      (node (ref "C24") (pin "2") (pinfunction "2_2") (pintype "passive"))
      (node (ref "C25") (pin "2") (pinfunction "2_2") (pintype "passive"))
      (node (ref "C26") (pin "2") (pinfunction "2_2") (pintype "passive"))
      (node (ref "C27") (pin "2") (pinfunction "2_2") (pintype "passive"))
      (node (ref "C28") (pin "2") (pinfunction "2_2") (pintype "passive"))
      (node (ref "C3") (pin "2") (pinfunction "2_2") (pintype "passive"))
      (node (ref "C4") (pin "1") (pinfunction "1_1") (pintype "passive"))
      (node (ref "C5") (pin "1") (pinfunction "1_1") (pintype "passive"))
      (node (ref "C55") (pin "2") (pinfunction "2_2") (pintype "passive"))
      (node (ref "C56") (pin "2") (pinfunction "2_2") (pintype "passive"))
      (node (ref "C58") (pin "2") (pinfunction "2_2") (pintype "passive"))
      (node (ref "C59") (pin "2") (pinfunction "2_2") (pintype "passive"))
      (node (ref "C6") (pin "2") (pinfunction "2_2") (pintype "passive"))
      (node (ref "C62") (pin "1") (pinfunction "1_1") (pintype "passive"))
      (node (ref "C64") (pin "1") (pinfunction "1_1") (pintype "passive"))
      (node (ref "C65") (pin "1") (pinfunction "1_1") (pintype "passive"))
      (node (ref "C7") (pin "2") (pinfunction "2_2") (pintype "passive"))
      (node (ref "C8") (pin "1") (pinfunction "1_1") (pintype "passive"))
      (node (ref "C9") (pin "1") (pinfunction "1_1") (pintype "passive"))
      (node (ref "CON1") (pin "2") (pinfunction "GND_2") (pintype "power_in"))
      (node (ref "CON1") (pin "3") (pinfunction "GND_3") (pintype "power_in"))
      (node (ref "CON1") (pin "4") (pinfunction "GND_4") (pintype "power_in"))
      (node (ref "CON1") (pin "5") (pinfunction "GND_5") (pintype "power_in"))
      (node (ref "GND") (pin "1") (pinfunction "TP_1") (pintype "passive"))
      (node (ref "J1") (pin "3") (pinfunction "3_3") (pintype "passive"))
      (node (ref "J1") (pin "5") (pinfunction "5_5") (pintype "passive"))
      (node (ref "J1") (pin "9") (pinfunction "9_9") (pintype "passive"))
      (node (ref "NTC1") (pin "1") (pintype "passive"))
      (node (ref "P1") (pin "3") (pinfunction "3_3") (pintype "passive"))
      (node (ref "P2") (pin "5") (pinfunction "5_5") (pintype "passive"))
      (node (ref "P2") (pin "6") (pinfunction "6_6") (pintype "passive"))
      (node (ref "R3") (pin "2") (pinfunction "2_2") (pintype "passive"))
      (node (ref "R41") (pin "1") (pinfunction "1_1") (pintype "passive"))
      (node (ref "U1") (pin "102") (pinfunction "VSS_7_102") (pintype "power_in"))
      (node (ref "U1") (pin "113") (pinfunction "VSS_8_113") (pintype "power_in"))
      (node (ref "U1") (pin "126") (pinfunction "VSS_9_126") (pintype "power_in"))
      (node (ref "U1") (pin "135") (pinfunction "VSS_10_135") (pintype "power_in"))
      (node (ref "U1") (pin "14") (pinfunction "VSS_1_14") (pintype "power_in"))
      (node (ref "U1") (pin "148") (pinfunction "VSS_11_148") (pintype "power_in"))
      (node (ref "U1") (pin "158") (pinfunction "VSS_12_158") (pintype "power_in"))
      (node (ref "U1") (pin "22") (pinfunction "VSS_2_22") (pintype "power_in"))
      (node (ref "U1") (pin "37") (pinfunction "VSSA_37") (pintype "power_in"))
      (node (ref "U1") (pin "48") (pinfunction "VSS_3_48") (pintype "power_in"))
      (node (ref "U1") (pin "61") (pinfunction "VSS_4_61") (pintype "power_in"))
      (node (ref "U1") (pin "71") (pinfunction "VSS_5_71") (pintype "power_in"))
      (node (ref "U1") (pin "90") (pinfunction "VSS_6_90") (pintype "power_in"))
      (node (ref "U10") (pin "11") (pinfunction "GND_11") (pintype "power_in"))
      (node (ref "U11") (pin "1") (pinfunction "GND_1") (pintype "passive"))
      (node (ref "U11") (pin "10") (pinfunction "GND_10") (pintype "passive"))
      (node (ref "U11") (pin "12") (pinfunction "GND_12") (pintype "passive"))
      (node (ref "U13") (pin "2") (pinfunction "SDIX_2") (pintype "bidirectional"))
      (node (ref "U13") (pin "3") (pinfunction "SCX_3") (pintype "bidirectional"))
      (node (ref "U13") (pin "6") (pinfunction "GND@6_6") (pintype "bidirectional"))
      (node (ref "U13") (pin "7") (pinfunction "GND@7_7") (pintype "bidirectional"))
      (node (ref "U16") (pin "11") (pinfunction "11_11") (pintype "power_in"))
      (node (ref "U16") (pin "13") (pinfunction "13_13") (pintype "power_in"))
      (node (ref "U16") (pin "15") (pinfunction "15_15") (pintype "power_in"))
      (node (ref "U16") (pin "9") (pinfunction "9_9") (pintype "power_in"))
      (node (ref "U2") (pin "2") (pinfunction "2_2") (pintype "passive"))
      (node (ref "U2") (pin "4") (pinfunction "4_4") (pintype "power_in"))
      (node (ref "U2") (pin "6") (pinfunction "6_6") (pintype "power_in"))
      (node (ref "U2") (pin "8") (pinfunction "8_8") (pintype "power_in"))
      (node (ref "X2") (pin "2") (pinfunction "2_2") (pintype "passive"))
      (node (ref "X2") (pin "4") (pinfunction "4_4") (pintype "passive"))
    )
    (net (code "80") (name "Net-(CON1-Signal)") (class "Default")
      (node (ref "C57") (pin "1") (pinfunction "1_1") (pintype "passive"))
      (node (ref "CON1") (pin "1") (pinfunction "Signal_1") (pintype "passive"))
      (node (ref "L7") (pin "2") (pinfunction "2_2") (pintype "passive"))
    )
    (net (code "81") (name "Net-(J1-Pad1)") (class "Default")
      (node (ref "J1") (pin "1") (pinfunction "1_1") (pintype "passive"))
      (node (ref "R37") (pin "1") (pinfunction "1_1") (pintype "passive"))
    )
    (net (code "82") (name "Net-(L7-Pad1)") (class "Default")
      (node (ref "L7") (pin "1") (pinfunction "1_1") (pintype "passive"))
      (node (ref "R2") (pin "2") (pinfunction "2_2") (pintype "passive"))
    )
    (net (code "83") (name "Net-(LED1-ANODE)") (class "Default")
      (node (ref "LED1") (pin "1") (pinfunction "ANODE_1") (pintype "passive"))
      (node (ref "R25") (pin "2") (pinfunction "2_2") (pintype "passive"))
    )
    (net (code "84") (name "Net-(LED2-ANODE)") (class "Default")
      (node (ref "LED2") (pin "1") (pinfunction "ANODE_1") (pintype "passive"))
      (node (ref "R26") (pin "2") (pinfunction "2_2") (pintype "passive"))
    )
    (net (code "85") (name "Net-(LED3-ANODE)") (class "Default")
      (node (ref "LED3") (pin "1") (pinfunction "ANODE_1") (pintype "passive"))
      (node (ref "R27") (pin "2") (pinfunction "2_2") (pintype "passive"))
    )
    (net (code "86") (name "Net-(LED4-ANODE)") (class "Default")
      (node (ref "LED4") (pin "1") (pinfunction "ANODE_1") (pintype "passive"))
      (node (ref "R28") (pin "2") (pinfunction "2_2") (pintype "passive"))
    )
    (net (code "87") (name "Net-(P4-Pad1)") (class "Default")
      (node (ref "P4") (pin "1") (pinfunction "1_1") (pintype "bidirectional"))
      (node (ref "U2") (pin "15") (pinfunction "15_15") (pintype "power_in"))
    )
    (net (code "88") (name "Net-(P4-Pad2)") (class "Default")
      (node (ref "P4") (pin "2") (pinfunction "2_2") (pintype "bidirectional"))
      (node (ref "U2") (pin "16") (pinfunction "16_16") (pintype "power_in"))
    )
    (net (code "89") (name "Net-(P7-Pad1)") (class "Default")
      (node (ref "P7") (pin "1") (pinfunction "1_1") (pintype "bidirectional"))
      (node (ref "U2") (pin "13") (pinfunction "13_13") (pintype "power_in"))
    )
    (net (code "90") (name "Net-(P7-Pad2)") (class "Default")
      (node (ref "P7") (pin "2") (pinfunction "2_2") (pintype "bidirectional"))
      (node (ref "U2") (pin "14") (pinfunction "14_14") (pintype "power_in"))
    )
    (net (code "91") (name "Net-(P8-Pad1)") (class "Default")
      (node (ref "P8") (pin "1") (pinfunction "1_1") (pintype "bidirectional"))
      (node (ref "U2") (pin "11") (pinfunction "11_11") (pintype "power_in"))
    )
    (net (code "92") (name "Net-(P8-Pad2)") (class "Default")
      (node (ref "P8") (pin "2") (pinfunction "2_2") (pintype "bidirectional"))
      (node (ref "U2") (pin "12") (pinfunction "12_12") (pintype "power_in"))
    )
    (net (code "93") (name "Net-(P9-Pad1)") (class "Default")
      (node (ref "P9") (pin "1") (pinfunction "1_1") (pintype "bidirectional"))
      (node (ref "U2") (pin "9") (pinfunction "9_9") (pintype "power_in"))
    )
    (net (code "94") (name "Net-(P9-Pad2)") (class "Default")
      (node (ref "P9") (pin "2") (pinfunction "2_2") (pintype "bidirectional"))
      (node (ref "U2") (pin "10") (pinfunction "10_10") (pintype "power_in"))
    )
    (net (code "95") (name "Net-(P10-Pad1)") (class "Default")
      (node (ref "P10") (pin "1") (pinfunction "1_1") (pintype "bidirectional"))
      (node (ref "R32") (pin "1") (pinfunction "1_1") (pintype "passive"))
    )
    (net (code "96") (name "Net-(P10-Pad2)") (class "Default")
      (node (ref "P10") (pin "2") (pinfunction "2_2") (pintype "bidirectional"))
      (node (ref "U16") (pin "2") (pinfunction "2_2") (pintype "passive"))
    )
    (net (code "97") (name "Net-(P11-Pad1)") (class "Default")
      (node (ref "P11") (pin "1") (pinfunction "1_1") (pintype "bidirectional"))
      (node (ref "R34") (pin "1") (pinfunction "1_1") (pintype "passive"))
    )
    (net (code "98") (name "Net-(P11-Pad2)") (class "Default")
      (node (ref "P11") (pin "2") (pinfunction "2_2") (pintype "bidirectional"))
      (node (ref "U16") (pin "4") (pinfunction "4_4") (pintype "power_in"))
    )
    (net (code "99") (name "Net-(P12-Pad1)") (class "Default")
      (node (ref "P12") (pin "1") (pinfunction "1_1") (pintype "bidirectional"))
      (node (ref "R62") (pin "1") (pinfunction "1_1") (pintype "passive"))
    )
    (net (code "100") (name "Net-(P12-Pad2)") (class "Default")
      (node (ref "P12") (pin "2") (pinfunction "2_2") (pintype "bidirectional"))
      (node (ref "U16") (pin "6") (pinfunction "6_6") (pintype "power_in"))
    )
    (net (code "101") (name "Net-(P13-Pad1)") (class "Default")
      (node (ref "P13") (pin "1") (pinfunction "1_1") (pintype "bidirectional"))
      (node (ref "R64") (pin "1") (pinfunction "1_1") (pintype "passive"))
    )
    (net (code "102") (name "Net-(P13-Pad2)") (class "Default")
      (node (ref "P13") (pin "2") (pinfunction "2_2") (pintype "bidirectional"))
      (node (ref "U16") (pin "8") (pinfunction "8_8") (pintype "power_in"))
    )
    (net (code "103") (name "Net-(R9-Pad2)") (class "Default")
      (node (ref "R9") (pin "2") (pinfunction "2_2") (pintype "passive"))
      (node (ref "U2") (pin "1") (pinfunction "1_1") (pintype "passive"))
    )
    (net (code "104") (name "Net-(R10-Pad2)") (class "Default")
      (node (ref "R10") (pin "2") (pinfunction "2_2") (pintype "passive"))
      (node (ref "U2") (pin "3") (pinfunction "3_3") (pintype "passive"))
    )
    (net (code "105") (name "Net-(R16-Pad2)") (class "Default")
      (node (ref "R16") (pin "2") (pinfunction "2_2") (pintype "passive"))
      (node (ref "U2") (pin "5") (pinfunction "5_5") (pintype "power_in"))
    )
    (net (code "106") (name "Net-(R21-Pad2)") (class "Default")
      (node (ref "R21") (pin "2") (pinfunction "2_2") (pintype "passive"))
      (node (ref "U2") (pin "7") (pinfunction "7_7") (pintype "power_in"))
    )
    (net (code "107") (name "Net-(R32-Pad2)") (class "Default")
      (node (ref "R32") (pin "2") (pinfunction "2_2") (pintype "passive"))
      (node (ref "U16") (pin "1") (pinfunction "1_1") (pintype "passive"))
    )
    (net (code "108") (name "Net-(R34-Pad2)") (class "Default")
      (node (ref "R34") (pin "2") (pinfunction "2_2") (pintype "passive"))
      (node (ref "U16") (pin "3") (pinfunction "3_3") (pintype "passive"))
    )
    (net (code "109") (name "Net-(R62-Pad2)") (class "Default")
      (node (ref "R62") (pin "2") (pinfunction "2_2") (pintype "passive"))
      (node (ref "U16") (pin "5") (pinfunction "5_5") (pintype "power_in"))
    )
    (net (code "110") (name "Net-(R64-Pad2)") (class "Default")
      (node (ref "R64") (pin "2") (pinfunction "2_2") (pintype "passive"))
      (node (ref "U16") (pin "7") (pinfunction "7_7") (pintype "power_in"))
    )
    (net (code "111") (name "Net-(U1-PA9)") (class "Default")
      (node (ref "R8") (pin "2") (pinfunction "2_2") (pintype "passive"))
      (node (ref "U1") (pin "120") (pinfunction "PA9_120") (pintype "passive"))
    )
    (net (code "112") (name "Net-(U1-PC14-OSC32_IN)") (class "Default")
      (node (ref "C1") (pin "1") (pinfunction "1_1") (pintype "passive"))
      (node (ref "U1") (pin "9") (pinfunction "PC14-OSC32_IN_9") (pintype "passive"))
      (node (ref "X1") (pin "2") (pinfunction "OSC2_2") (pintype "passive"))
    )
    (net (code "113") (name "Net-(U1-PC15-OSC32_OUT)") (class "Default")
      (node (ref "C3") (pin "1") (pinfunction "1_1") (pintype "passive"))
      (node (ref "U1") (pin "10") (pinfunction "PC15-OSC32_OUT_10") (pintype "passive"))
      (node (ref "X1") (pin "1") (pinfunction "OSC1_1") (pintype "passive"))
    )
    (net (code "114") (name "Net-(U1-PDR_ON)") (class "Default")
      (node (ref "R4") (pin "2") (pinfunction "2_2") (pintype "passive"))
      (node (ref "U1") (pin "171") (pinfunction "PDR_ON_171") (pintype "passive"))
    )
    (net (code "115") (name "Net-(U1-PH0-OSC_IN)") (class "Default")
      (node (ref "C6") (pin "1") (pinfunction "1_1") (pintype "passive"))
      (node (ref "U1") (pin "29") (pinfunction "PH0-OSC_IN_29") (pintype "passive"))
      (node (ref "X2") (pin "1") (pinfunction "1_1") (pintype "passive"))
    )
    (net (code "116") (name "Net-(U1-PH1-OSC_OUT)") (class "Default")
      (node (ref "C7") (pin "1") (pinfunction "1_1") (pintype "passive"))
      (node (ref "U1") (pin "30") (pinfunction "PH1-OSC_OUT_30") (pintype "passive"))
      (node (ref "X2") (pin "3") (pinfunction "2_3") (pintype "passive"))
    )
    (net (code "117") (name "Net-(U1-VBAT)") (class "Default")
      (node (ref "BT1") (pin "1") (pinfunction "1_1") (pintype "passive"))
      (node (ref "U1") (pin "6") (pinfunction "VBAT_6") (pintype "power_in"))
    )
    (net (code "118") (name "Net-(U11-RF_IN)") (class "Default")
      (node (ref "C57") (pin "2") (pinfunction "2_2") (pintype "passive"))
      (node (ref "U11") (pin "11") (pinfunction "RF_IN_11") (pintype "passive"))
    )
    (net (code "119") (name "VBUS_FS1") (class "Default")
      (node (ref "R8") (pin "1") (pinfunction "1_1") (pintype "passive"))
    )
    (net (code "120") (name "VDDA") (class "Default")
      (node (ref "C10") (pin "2") (pinfunction "2_2") (pintype "passive"))
      (node (ref "C11") (pin "2") (pinfunction "2_2") (pintype "passive"))
      (node (ref "C8") (pin "2") (pinfunction "2_2") (pintype "passive"))
      (node (ref "C9") (pin "2") (pinfunction "2_2") (pintype "passive"))
      (node (ref "FB1") (pin "2") (pinfunction "2_2") (pintype "passive"))
      (node (ref "U1") (pin "38") (pinfunction "VREF+_38") (pintype "passive"))
      (node (ref "U1") (pin "39") (pinfunction "VDDA_39") (pintype "power_in"))
    )
    (net (code "121") (name "VDD_MCU") (class "Default")
      (node (ref "C14") (pin "1") (pinfunction "1_1") (pintype "passive"))
      (node (ref "C15") (pin "1") (pinfunction "1_1") (pintype "passive"))
      (node (ref "C16") (pin "1") (pinfunction "1_1") (pintype "passive"))
      (node (ref "C17") (pin "1") (pinfunction "1_1") (pintype "passive"))
      (node (ref "C18") (pin "1") (pinfunction "1_1") (pintype "passive"))
      (node (ref "C19") (pin "1") (pinfunction "1_1") (pintype "passive"))
      (node (ref "C20") (pin "1") (pinfunction "1_1") (pintype "passive"))
      (node (ref "C21") (pin "1") (pinfunction "1_1") (pintype "passive"))
      (node (ref "C22") (pin "1") (pinfunction "1_1") (pintype "passive"))
      (node (ref "C23") (pin "1") (pinfunction "1_1") (pintype "passive"))
      (node (ref "C24") (pin "1") (pinfunction "1_1") (pintype "passive"))
      (node (ref "C25") (pin "1") (pinfunction "1_1") (pintype "passive"))
      (node (ref "C26") (pin "1") (pinfunction "1_1") (pintype "passive"))
      (node (ref "C27") (pin "1") (pinfunction "1_1") (pintype "passive"))
      (node (ref "C28") (pin "1") (pinfunction "1_1") (pintype "passive"))
      (node (ref "C4") (pin "2") (pinfunction "2_2") (pintype "passive"))
      (node (ref "C5") (pin "2") (pinfunction "2_2") (pintype "passive"))
      (node (ref "C55") (pin "1") (pinfunction "1_1") (pintype "passive"))
      (node (ref "C56") (pin "1") (pinfunction "1_1") (pintype "passive"))
      (node (ref "C59") (pin "1") (pinfunction "1_1") (pintype "passive"))
      (node (ref "C64") (pin "2") (pinfunction "2_2") (pintype "passive"))
      (node (ref "C65") (pin "2") (pinfunction "2_2") (pintype "passive"))
      (node (ref "FB1") (pin "1") (pinfunction "1_1") (pintype "passive"))
      (node (ref "R1") (pin "2") (pinfunction "2_2") (pintype "passive"))
      (node (ref "R11") (pin "1") (pinfunction "1_1") (pintype "passive"))
      (node (ref "R25") (pin "1") (pinfunction "1_1") (pintype "passive"))
      (node (ref "R26") (pin "1") (pinfunction "1_1") (pintype "passive"))
      (node (ref "R27") (pin "1") (pinfunction "1_1") (pintype "passive"))
      (node (ref "R28") (pin "1") (pinfunction "1_1") (pintype "passive"))
      (node (ref "R31") (pin "2") (pinfunction "2_2") (pintype "passive"))
      (node (ref "R33") (pin "2") (pinfunction "2_2") (pintype "passive"))
      (node (ref "R37") (pin "2") (pinfunction "2_2") (pintype "passive"))
      (node (ref "R4") (pin "1") (pinfunction "1_1") (pintype "passive"))
      (node (ref "R40") (pin "1") (pinfunction "1_1") (pintype "passive"))
      (node (ref "R61") (pin "2") (pinfunction "2_2") (pintype "passive"))
      (node (ref "R63") (pin "2") (pinfunction "2_2") (pintype "passive"))
      (node (ref "U1") (pin "103") (pinfunction "VDD_9_103") (pintype "power_in"))
      (node (ref "U1") (pin "114") (pinfunction "VDD33_USB_114") (pintype "power_in"))
      (node (ref "U1") (pin "127") (pinfunction "VDD_10_127") (pintype "power_in"))
      (node (ref "U1") (pin "136") (pinfunction "VDD_11_136") (pintype "power_in"))
      (node (ref "U1") (pin "149") (pinfunction "VDD_12_149") (pintype "power_in"))
      (node (ref "U1") (pin "15") (pinfunction "VDD_1_15") (pintype "power_in"))
      (node (ref "U1") (pin "159") (pinfunction "VDD_13_159") (pintype "power_in"))
      (node (ref "U1") (pin "172") (pinfunction "VDD_14_172") (pintype "power_in"))
      (node (ref "U1") (pin "23") (pinfunction "VDD_2_23") (pintype "power_in"))
      (node (ref "U1") (pin "36") (pinfunction "VDD_3_36") (pintype "power_in"))
      (node (ref "U1") (pin "49") (pinfunction "VDD_4_49") (pintype "power_in"))
      (node (ref "U1") (pin "62") (pinfunction "VDD_5_62") (pintype "power_in"))
      (node (ref "U1") (pin "72") (pinfunction "VDD_6_72") (pintype "power_in"))
      (node (ref "U1") (pin "82") (pinfunction "VDD_7_82") (pintype "power_in"))
      (node (ref "U1") (pin "91") (pinfunction "VDD_8_91") (pintype "power_in"))
      (node (ref "U10") (pin "19") (pinfunction "VCCB_19") (pintype "power_in"))
      (node (ref "U11") (pin "6") (pinfunction "V_BCKP_6") (pintype "passive"))
      (node (ref "U11") (pin "7") (pinfunction "VCC_IO_7") (pintype "passive"))
      (node (ref "U11") (pin "8") (pinfunction "VCC_8") (pintype "passive"))
      (node (ref "U13") (pin "5") (pinfunction "VDDIO_5") (pintype "bidirectional"))
      (node (ref "U13") (pin "8") (pinfunction "VDD_8") (pintype "bidirectional"))
    )
    (net (code "122") (name "unconnected-(J1-Pad7)") (class "Default")
      (node (ref "J1") (pin "7") (pinfunction "7_7") (pintype "passive+no_connect"))
    )
    (net (code "123") (name "unconnected-(P2-Pad1)") (class "Default")
      (node (ref "P2") (pin "1") (pinfunction "1_1") (pintype "passive+no_connect"))
    )
    (net (code "124") (name "unconnected-(P2-Pad2)") (class "Default")
      (node (ref "P2") (pin "2") (pinfunction "2_2") (pintype "passive+no_connect"))
    )
    (net (code "125") (name "unconnected-(P2-Pad3)") (class "Default")
      (node (ref "P2") (pin "3") (pinfunction "3_3") (pintype "passive+no_connect"))
    )
    (net (code "126") (name "unconnected-(P2-Pad4)") (class "Default")
      (node (ref "P2") (pin "4") (pinfunction "4_4") (pintype "passive+no_connect"))
    )
    (net (code "127") (name "unconnected-(U1-PA0-WKUP-Pad40)") (class "Default")
      (node (ref "U1") (pin "40") (pinfunction "PA0-WKUP_40") (pintype "passive"))
    )
    (net (code "128") (name "unconnected-(U1-PA3-Pad47)") (class "Default")
      (node (ref "U1") (pin "47") (pinfunction "PA3_47") (pintype "passive"))
    )
    (net (code "129") (name "unconnected-(U1-PA4-Pad50)") (class "Default")
      (node (ref "U1") (pin "50") (pinfunction "PA4_50") (pintype "passive"))
    )
    (net (code "130") (name "unconnected-(U1-PA5-Pad51)") (class "Default")
      (node (ref "U1") (pin "51") (pinfunction "PA5_51") (pintype "passive"))
    )
    (net (code "131") (name "unconnected-(U1-PA6-Pad52)") (class "Default")
      (node (ref "U1") (pin "52") (pinfunction "PA6_52") (pintype "passive"))
    )
    (net (code "132") (name "unconnected-(U1-PB0-Pad56)") (class "Default")
      (node (ref "U1") (pin "56") (pinfunction "PB0_56") (pintype "passive"))
    )
    (net (code "133") (name "unconnected-(U1-PB1-Pad57)") (class "Default")
      (node (ref "U1") (pin "57") (pinfunction "PB1_57") (pintype "passive"))
    )
    (net (code "134") (name "unconnected-(U1-PB2-Pad58)") (class "Default")
      (node (ref "U1") (pin "58") (pinfunction "PB2_58") (pintype "passive"))
    )
    (net (code "135") (name "unconnected-(U1-PB4-Pad162)") (class "Default")
      (node (ref "U1") (pin "162") (pinfunction "PB4_162") (pintype "passive"))
    )
    (net (code "136") (name "unconnected-(U1-PB5-Pad163)") (class "Default")
      (node (ref "U1") (pin "163") (pinfunction "PB5_163") (pintype "passive"))
    )
    (net (code "137") (name "unconnected-(U1-PB6-Pad164)") (class "Default")
      (node (ref "U1") (pin "164") (pinfunction "PB6_164") (pintype "passive"))
    )
    (net (code "138") (name "unconnected-(U1-PB7-Pad165)") (class "Default")
      (node (ref "U1") (pin "165") (pinfunction "PB7_165") (pintype "passive"))
    )
    (net (code "139") (name "unconnected-(U1-PB10-Pad79)") (class "Default")
      (node (ref "U1") (pin "79") (pinfunction "PB10_79") (pintype "passive"))
    )
    (net (code "140") (name "unconnected-(U1-PB11-Pad80)") (class "Default")
      (node (ref "U1") (pin "80") (pinfunction "PB11_80") (pintype "passive"))
    )
    (net (code "141") (name "unconnected-(U1-PC2_C-Pad34)") (class "Default")
      (node (ref "U1") (pin "34") (pinfunction "PC2_C_34") (pintype "passive"))
    )
    (net (code "142") (name "unconnected-(U1-PC3_C-Pad35)") (class "Default")
      (node (ref "U1") (pin "35") (pinfunction "PC3_C_35") (pintype "passive"))
    )
    (net (code "143") (name "unconnected-(U1-PC6-Pad115)") (class "Default")
      (node (ref "U1") (pin "115") (pinfunction "PC6_115") (pintype "passive"))
    )
    (net (code "144") (name "unconnected-(U1-PC7-Pad116)") (class "Default")
      (node (ref "U1") (pin "116") (pinfunction "PC7_116") (pintype "passive"))
    )
    (net (code "145") (name "unconnected-(U1-PC8-Pad117)") (class "Default")
      (node (ref "U1") (pin "117") (pinfunction "PC8_117") (pintype "passive"))
    )
    (net (code "146") (name "unconnected-(U1-PC9-Pad118)") (class "Default")
      (node (ref "U1") (pin "118") (pinfunction "PC9_118") (pintype "passive"))
    )
    (net (code "147") (name "unconnected-(U1-PD1-Pad143)") (class "Default")
      (node (ref "U1") (pin "143") (pinfunction "PD1_143") (pintype "passive"))
    )
    (net (code "148") (name "unconnected-(U1-PD2-Pad144)") (class "Default")
      (node (ref "U1") (pin "144") (pinfunction "PD2_144") (pintype "passive"))
    )
    (net (code "149") (name "unconnected-(U1-PD3-Pad145)") (class "Default")
      (node (ref "U1") (pin "145") (pinfunction "PD3_145") (pintype "passive"))
    )
    (net (code "150") (name "unconnected-(U1-PD4-Pad146)") (class "Default")
      (node (ref "U1") (pin "146") (pinfunction "PD4_146") (pintype "passive"))
    )
    (net (code "151") (name "unconnected-(U1-PD5-Pad147)") (class "Default")
      (node (ref "U1") (pin "147") (pinfunction "PD5_147") (pintype "passive"))
    )
    (net (code "152") (name "unconnected-(U1-PD6-Pad150)") (class "Default")
      (node (ref "U1") (pin "150") (pinfunction "PD6_150") (pintype "passive"))
    )
    (net (code "153") (name "unconnected-(U1-PD7-Pad151)") (class "Default")
      (node (ref "U1") (pin "151") (pinfunction "PD7_151") (pintype "passive"))
    )
    (net (code "154") (name "unconnected-(U1-PD8-Pad96)") (class "Default")
      (node (ref "U1") (pin "96") (pinfunction "PD8_96") (pintype "passive"))
    )
    (net (code "155") (name "unconnected-(U1-PD9-Pad97)") (class "Default")
      (node (ref "U1") (pin "97") (pinfunction "PD9_97") (pintype "passive"))
    )
    (net (code "156") (name "unconnected-(U1-PD10-Pad98)") (class "Default")
      (node (ref "U1") (pin "98") (pinfunction "PD10_98") (pintype "passive"))
    )
    (net (code "157") (name "unconnected-(U1-PD11-Pad99)") (class "Default")
      (node (ref "U1") (pin "99") (pinfunction "PD11_99") (pintype "passive"))
    )
    (net (code "158") (name "unconnected-(U1-PD12-Pad100)") (class "Default")
      (node (ref "U1") (pin "100") (pinfunction "PD12_100") (pintype "passive"))
    )
    (net (code "159") (name "unconnected-(U1-PD13-Pad101)") (class "Default")
      (node (ref "U1") (pin "101") (pinfunction "PD13_101") (pintype "passive"))
    )
    (net (code "160") (name "unconnected-(U1-PD14-Pad104)") (class "Default")
      (node (ref "U1") (pin "104") (pinfunction "PD14_104") (pintype "passive"))
    )
    (net (code "161") (name "unconnected-(U1-PD15-Pad105)") (class "Default")
      (node (ref "U1") (pin "105") (pinfunction "PD15_105") (pintype "passive"))
    )
    (net (code "162") (name "unconnected-(U1-PE0-Pad169)") (class "Default")
      (node (ref "U1") (pin "169") (pinfunction "PE0_169") (pintype "passive"))
    )
    (net (code "163") (name "unconnected-(U1-PE1-Pad170)") (class "Default")
      (node (ref "U1") (pin "170") (pinfunction "PE1_170") (pintype "passive"))
    )
    (net (code "164") (name "unconnected-(U1-PE10-Pad73)") (class "Default")
      (node (ref "U1") (pin "73") (pinfunction "PE10_73") (pintype "passive"))
    )
    (net (code "165") (name "unconnected-(U1-PE15-Pad78)") (class "Default")
      (node (ref "U1") (pin "78") (pinfunction "PE15_78") (pintype "passive"))
    )
    (net (code "166") (name "unconnected-(U1-PF0-Pad16)") (class "Default")
      (node (ref "U1") (pin "16") (pinfunction "PF0_16") (pintype "passive"))
    )
    (net (code "167") (name "unconnected-(U1-PF1-Pad17)") (class "Default")
      (node (ref "U1") (pin "17") (pinfunction "PF1_17") (pintype "passive"))
    )
    (net (code "168") (name "unconnected-(U1-PF2-Pad18)") (class "Default")
      (node (ref "U1") (pin "18") (pinfunction "PF2_18") (pintype "passive"))
    )
    (net (code "169") (name "unconnected-(U1-PF3-Pad19)") (class "Default")
      (node (ref "U1") (pin "19") (pinfunction "PF3_19") (pintype "passive"))
    )
    (net (code "170") (name "unconnected-(U1-PF6-Pad24)") (class "Default")
      (node (ref "U1") (pin "24") (pinfunction "PF6_24") (pintype "passive"))
    )
    (net (code "171") (name "unconnected-(U1-PF7-Pad25)") (class "Default")
      (node (ref "U1") (pin "25") (pinfunction "PF7_25") (pintype "passive"))
    )
    (net (code "172") (name "unconnected-(U1-PF8-Pad26)") (class "Default")
      (node (ref "U1") (pin "26") (pinfunction "PF8_26") (pintype "passive"))
    )
    (net (code "173") (name "unconnected-(U1-PF9-Pad27)") (class "Default")
      (node (ref "U1") (pin "27") (pinfunction "PF9_27") (pintype "passive"))
    )
    (net (code "174") (name "unconnected-(U1-PF10-Pad28)") (class "Default")
      (node (ref "U1") (pin "28") (pinfunction "PF10_28") (pintype "passive"))
    )
    (net (code "175") (name "unconnected-(U1-PF11-Pad59)") (class "Default")
      (node (ref "U1") (pin "59") (pinfunction "PF11_59") (pintype "passive"))
    )
    (net (code "176") (name "unconnected-(U1-PF12-Pad60)") (class "Default")
      (node (ref "U1") (pin "60") (pinfunction "PF12_60") (pintype "passive"))
    )
    (net (code "177") (name "unconnected-(U1-PF13-Pad63)") (class "Default")
      (node (ref "U1") (pin "63") (pinfunction "PF13_63") (pintype "passive"))
    )
    (net (code "178") (name "unconnected-(U1-PF14-Pad64)") (class "Default")
      (node (ref "U1") (pin "64") (pinfunction "PF14_64") (pintype "passive"))
    )
    (net (code "179") (name "unconnected-(U1-PF15-Pad65)") (class "Default")
      (node (ref "U1") (pin "65") (pinfunction "PF15_65") (pintype "passive"))
    )
    (net (code "180") (name "unconnected-(U1-PG3-Pad107)") (class "Default")
      (node (ref "U1") (pin "107") (pinfunction "PG3_107") (pintype "passive"))
    )
    (net (code "181") (name "unconnected-(U1-PG4-Pad108)") (class "Default")
      (node (ref "U1") (pin "108") (pinfunction "PG4_108") (pintype "passive"))
    )
    (net (code "182") (name "unconnected-(U1-PG5-Pad109)") (class "Default")
      (node (ref "U1") (pin "109") (pinfunction "PG5_109") (pintype "passive"))
    )
    (net (code "183") (name "unconnected-(U1-PG6-Pad110)") (class "Default")
      (node (ref "U1") (pin "110") (pinfunction "PG6_110") (pintype "passive"))
    )
    (net (code "184") (name "unconnected-(U1-PG7-Pad111)") (class "Default")
      (node (ref "U1") (pin "111") (pinfunction "PG7_111") (pintype "passive"))
    )
    (net (code "185") (name "unconnected-(U1-PG8-Pad112)") (class "Default")
      (node (ref "U1") (pin "112") (pinfunction "PG8_112") (pintype "passive"))
    )
    (net (code "186") (name "unconnected-(U1-PG9-Pad152)") (class "Default")
      (node (ref "U1") (pin "152") (pinfunction "PG9_152") (pintype "passive"))
    )
    (net (code "187") (name "unconnected-(U1-PG14-Pad157)") (class "Default")
      (node (ref "U1") (pin "157") (pinfunction "PG14_157") (pintype "passive"))
    )
    (net (code "188") (name "unconnected-(U1-PG15-Pad160)") (class "Default")
      (node (ref "U1") (pin "160") (pinfunction "PG15_160") (pintype "passive"))
    )
    (net (code "189") (name "unconnected-(U1-PH2-Pad43)") (class "Default")
      (node (ref "U1") (pin "43") (pinfunction "PH2_43") (pintype "passive"))
    )
    (net (code "190") (name "unconnected-(U1-PH3-Pad44)") (class "Default")
      (node (ref "U1") (pin "44") (pinfunction "PH3_44") (pintype "passive"))
    )
    (net (code "191") (name "unconnected-(U1-PH4-Pad45)") (class "Default")
      (node (ref "U1") (pin "45") (pinfunction "PH4_45") (pintype "passive"))
    )
    (net (code "192") (name "unconnected-(U1-PH5-Pad46)") (class "Default")
      (node (ref "U1") (pin "46") (pinfunction "PH5_46") (pintype "passive"))
    )
    (net (code "193") (name "unconnected-(U1-PH6-Pad83)") (class "Default")
      (node (ref "U1") (pin "83") (pinfunction "PH6_83") (pintype "passive"))
    )
    (net (code "194") (name "unconnected-(U1-PH15-Pad130)") (class "Default")
      (node (ref "U1") (pin "130") (pinfunction "PH15_130") (pintype "passive"))
    )
    (net (code "195") (name "unconnected-(U1-PI0-Pad131)") (class "Default")
      (node (ref "U1") (pin "131") (pinfunction "PI0_131") (pintype "passive"))
    )
    (net (code "196") (name "unconnected-(U1-PI1-Pad132)") (class "Default")
      (node (ref "U1") (pin "132") (pinfunction "PI1_132") (pintype "passive"))
    )
    (net (code "197") (name "unconnected-(U1-PI3-Pad134)") (class "Default")
      (node (ref "U1") (pin "134") (pinfunction "PI3_134") (pintype "passive"))
    )
    (net (code "198") (name "unconnected-(U1-PI4-Pad173)") (class "Default")
      (node (ref "U1") (pin "173") (pinfunction "PI4_173") (pintype "passive"))
    )
    (net (code "199") (name "unconnected-(U1-PI5-Pad174)") (class "Default")
      (node (ref "U1") (pin "174") (pinfunction "PI5_174") (pintype "passive"))
    )
    (net (code "200") (name "unconnected-(U1-PI6-Pad175)") (class "Default")
      (node (ref "U1") (pin "175") (pinfunction "PI6_175") (pintype "passive"))
    )
    (net (code "201") (name "unconnected-(U1-PI7-Pad176)") (class "Default")
      (node (ref "U1") (pin "176") (pinfunction "PI7_176") (pintype "passive"))
    )
    (net (code "202") (name "unconnected-(U1-PI9-Pad11)") (class "Default")
      (node (ref "U1") (pin "11") (pinfunction "PI9_11") (pintype "passive"))
    )
    (net (code "203") (name "unconnected-(U1-PI10-Pad12)") (class "Default")
      (node (ref "U1") (pin "12") (pinfunction "PI10_12") (pintype "passive"))
    )
    (net (code "204") (name "unconnected-(U10-A2-Pad3)") (class "Default")
      (node (ref "U10") (pin "3") (pinfunction "A2_3") (pintype "bidirectional"))
    )
    (net (code "205") (name "unconnected-(U10-B2-Pad18)") (class "Default")
      (node (ref "U10") (pin "18") (pinfunction "B2_18") (pintype "bidirectional"))
    )
    (net (code "206") (name "unconnected-(U11-ANT_ON{slash}RSVD-Pad13)") (class "Default")
      (node (ref "U11") (pin "13") (pinfunction "ANT_ON/RSVD_13") (pintype "passive+no_connect"))
    )
    (net (code "207") (name "unconnected-(U11-EXTINT-Pad5)") (class "Default")
      (node (ref "U11") (pin "5") (pinfunction "EXTINT_5") (pintype "passive+no_connect"))
    )
    (net (code "208") (name "unconnected-(U11-RSVD-Pad18)") (class "Default")
      (node (ref "U11") (pin "18") (pinfunction "RSVD_18") (pintype "passive+no_connect"))
    )
    (net (code "209") (name "unconnected-(U11-SCL-Pad17)") (class "Default")
      (node (ref "U11") (pin "17") (pinfunction "SCL_17") (pintype "passive+no_connect"))
    )
    (net (code "210") (name "unconnected-(U11-SDA-Pad16)") (class "Default")
      (node (ref "U11") (pin "16") (pinfunction "SDA_16") (pintype "passive+no_connect"))
    )
    (net (code "211") (name "unconnected-(U11-V_ANT{slash}RSVD-Pad15)") (class "Default")
      (node (ref "U11") (pin "15") (pinfunction "V_ANT/RSVD_15") (pintype "passive+no_connect"))
    )
    (net (code "212") (name "unconnected-(U13-INT1-Pad4)") (class "Default")
      (node (ref "U13") (pin "4") (pinfunction "INT1_4") (pintype "bidirectional+no_connect"))
    )
    (net (code "213") (name "unconnected-(U13-INT2-Pad9)") (class "Default")
      (node (ref "U13") (pin "9") (pinfunction "INT2_9") (pintype "bidirectional+no_connect"))
    )
    (net (code "214") (name "unconnected-(U13-OCSX-Pad10)") (class "Default")
      (node (ref "U13") (pin "10") (pinfunction "OCSX_10") (pintype "bidirectional+no_connect"))
    )
    (net (code "215") (name "unconnected-(U13-SDOX-Pad11)") (class "Default")
      (node (ref "U13") (pin "11") (pinfunction "SDOX_11") (pintype "bidirectional+no_connect"))
    )
  )
)
